# MAIN_BORAD.net
KiCad netlist of a schematic drawn in Altium Designer
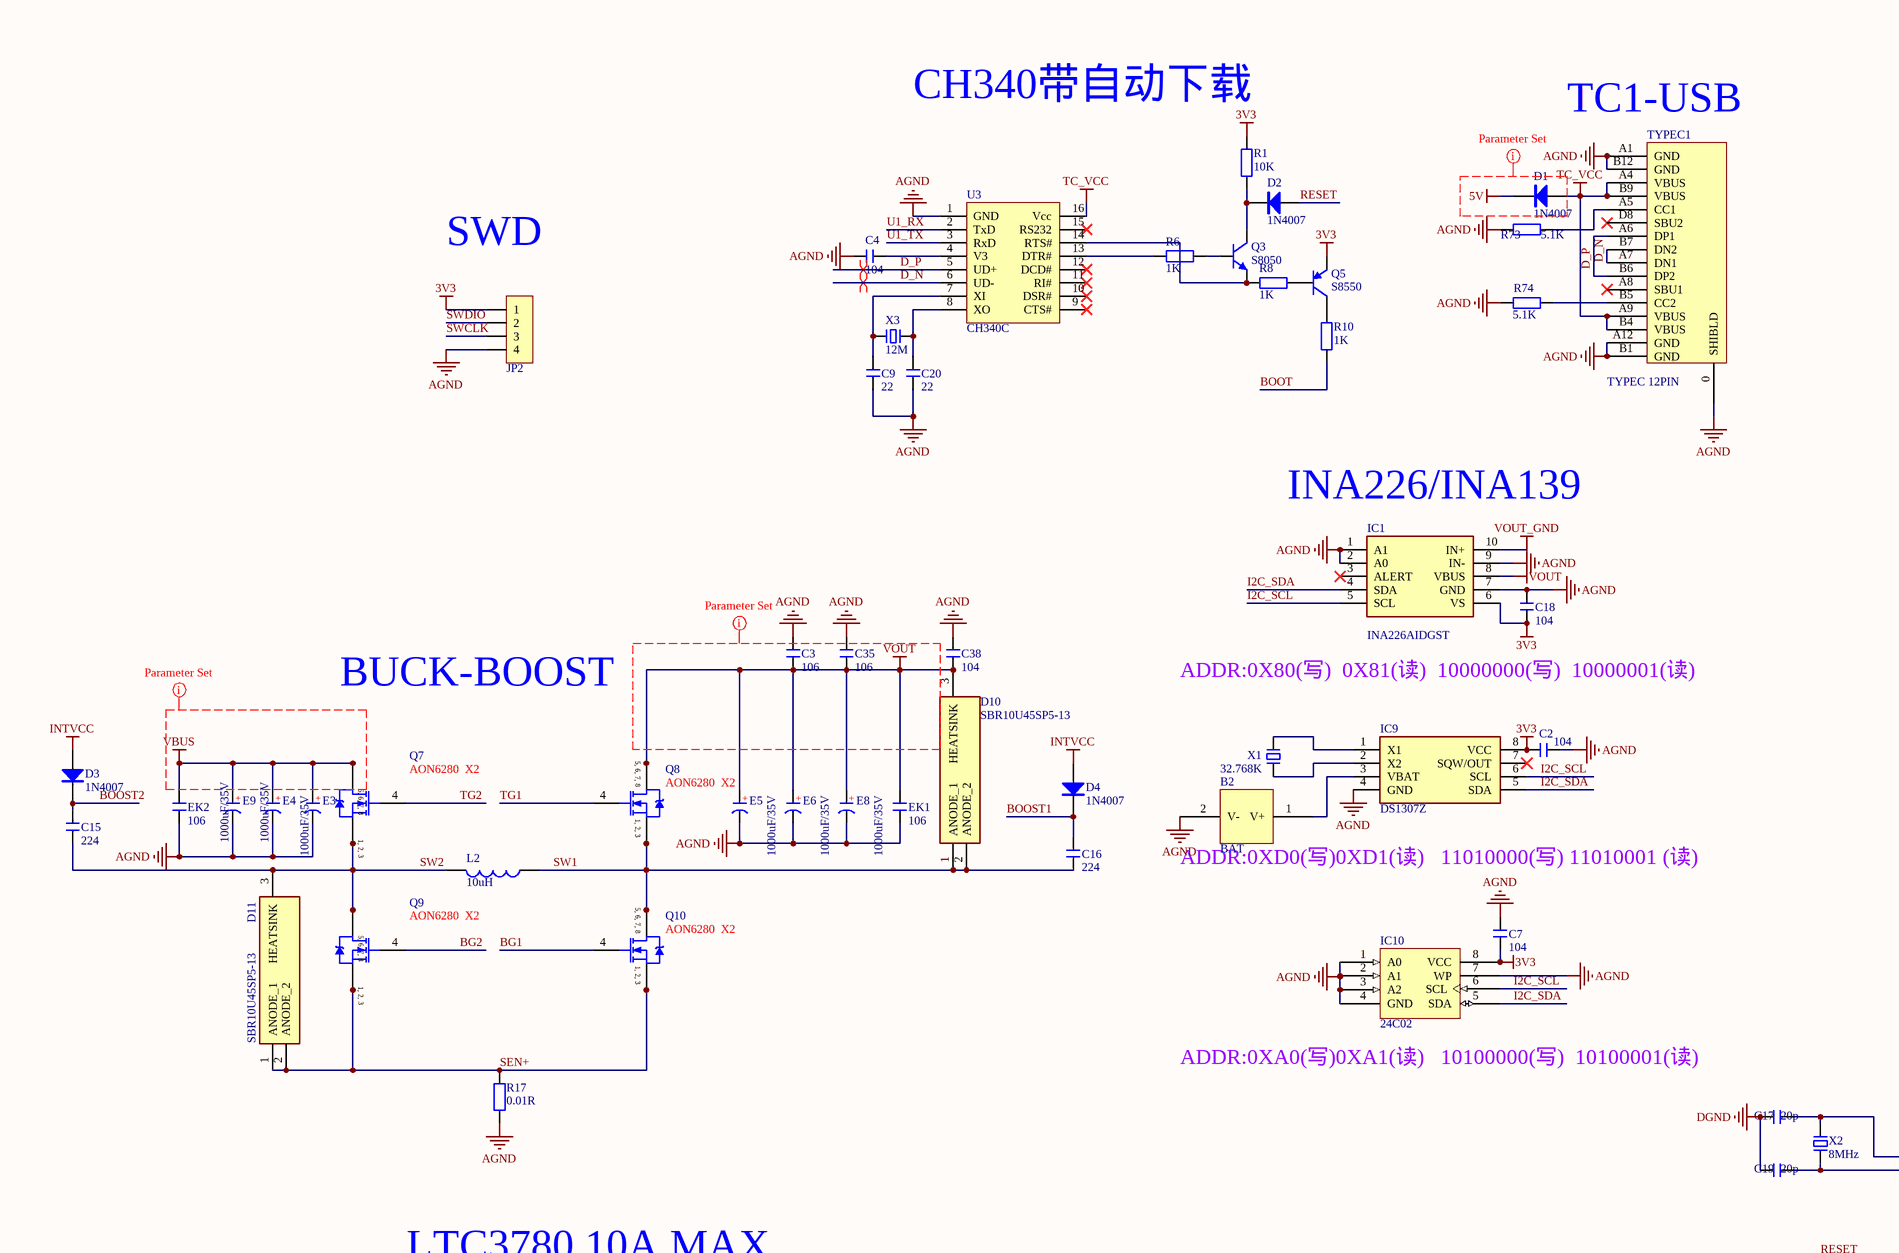
[diagram p0: MAIN_BORAD.SchDoc, top left]
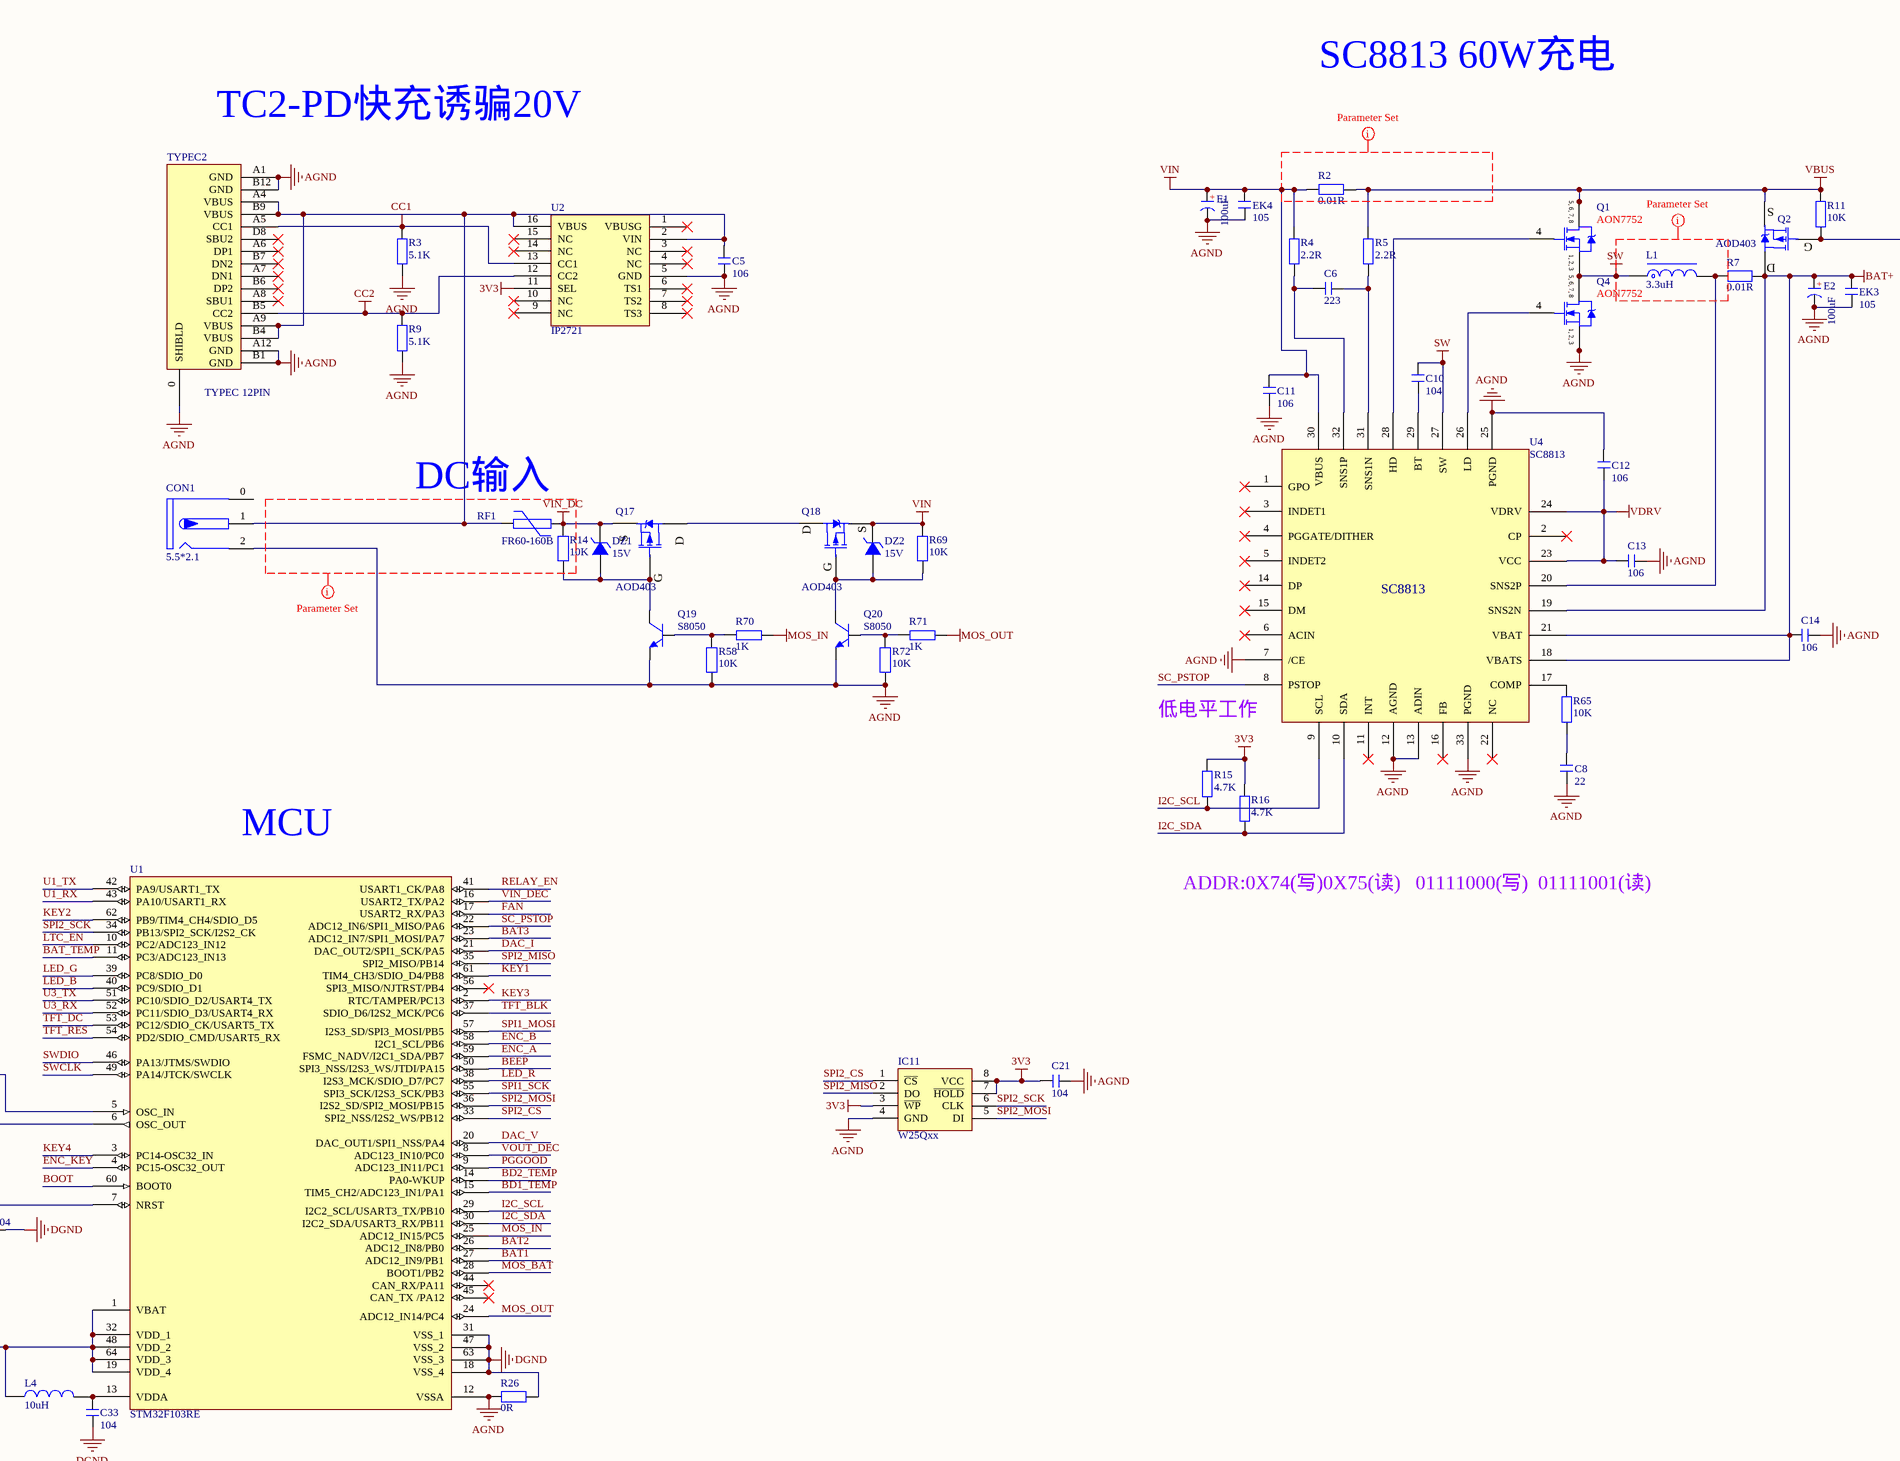
[diagram p1: MAIN_BORAD.SchDoc, top middle]
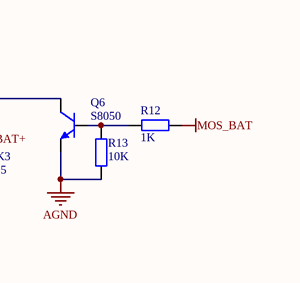
[diagram p2: MAIN_BORAD.SchDoc, top right]
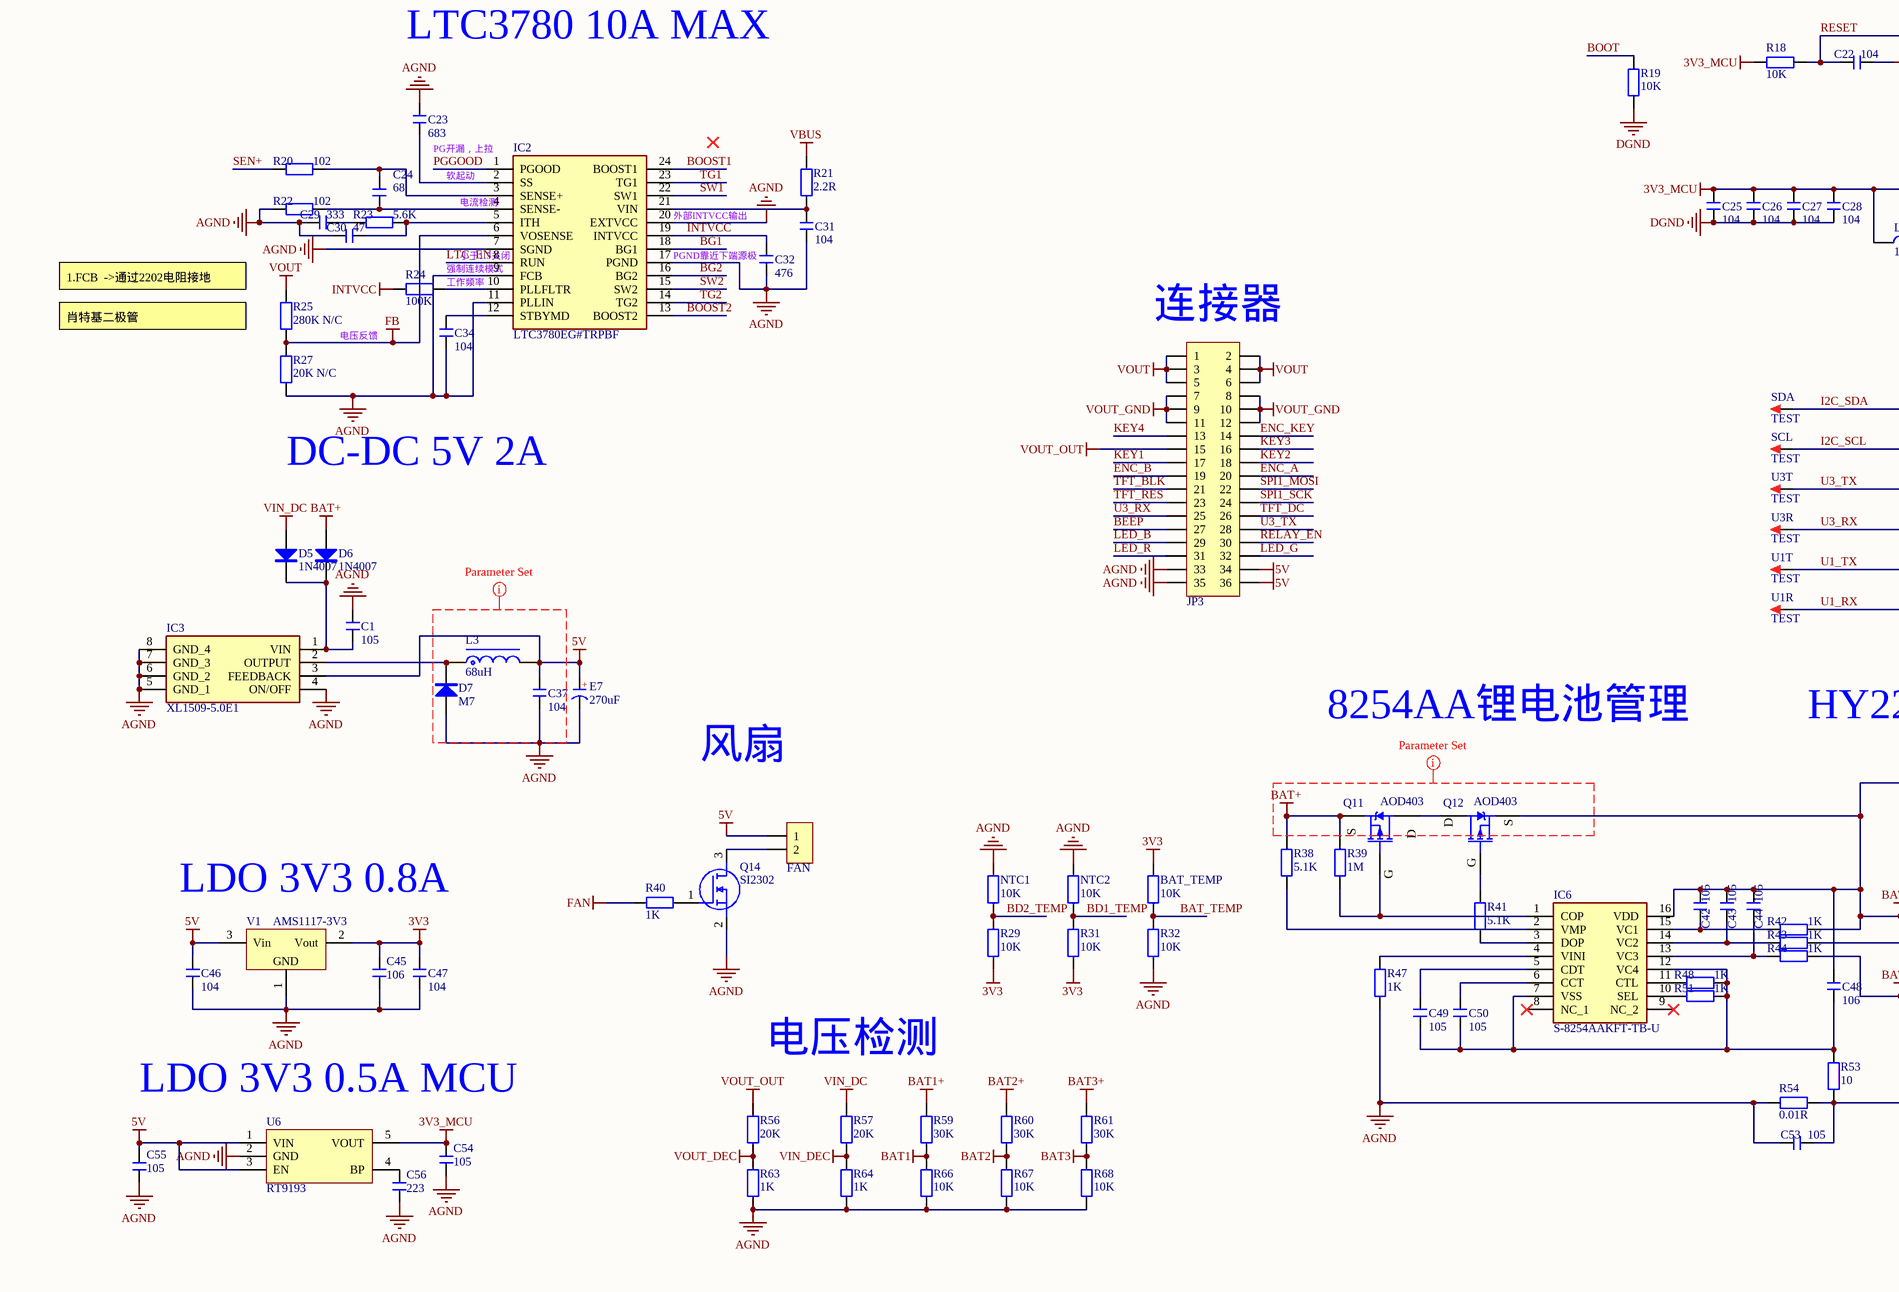
[diagram p3: MAIN_BORAD.SchDoc, bottom left]
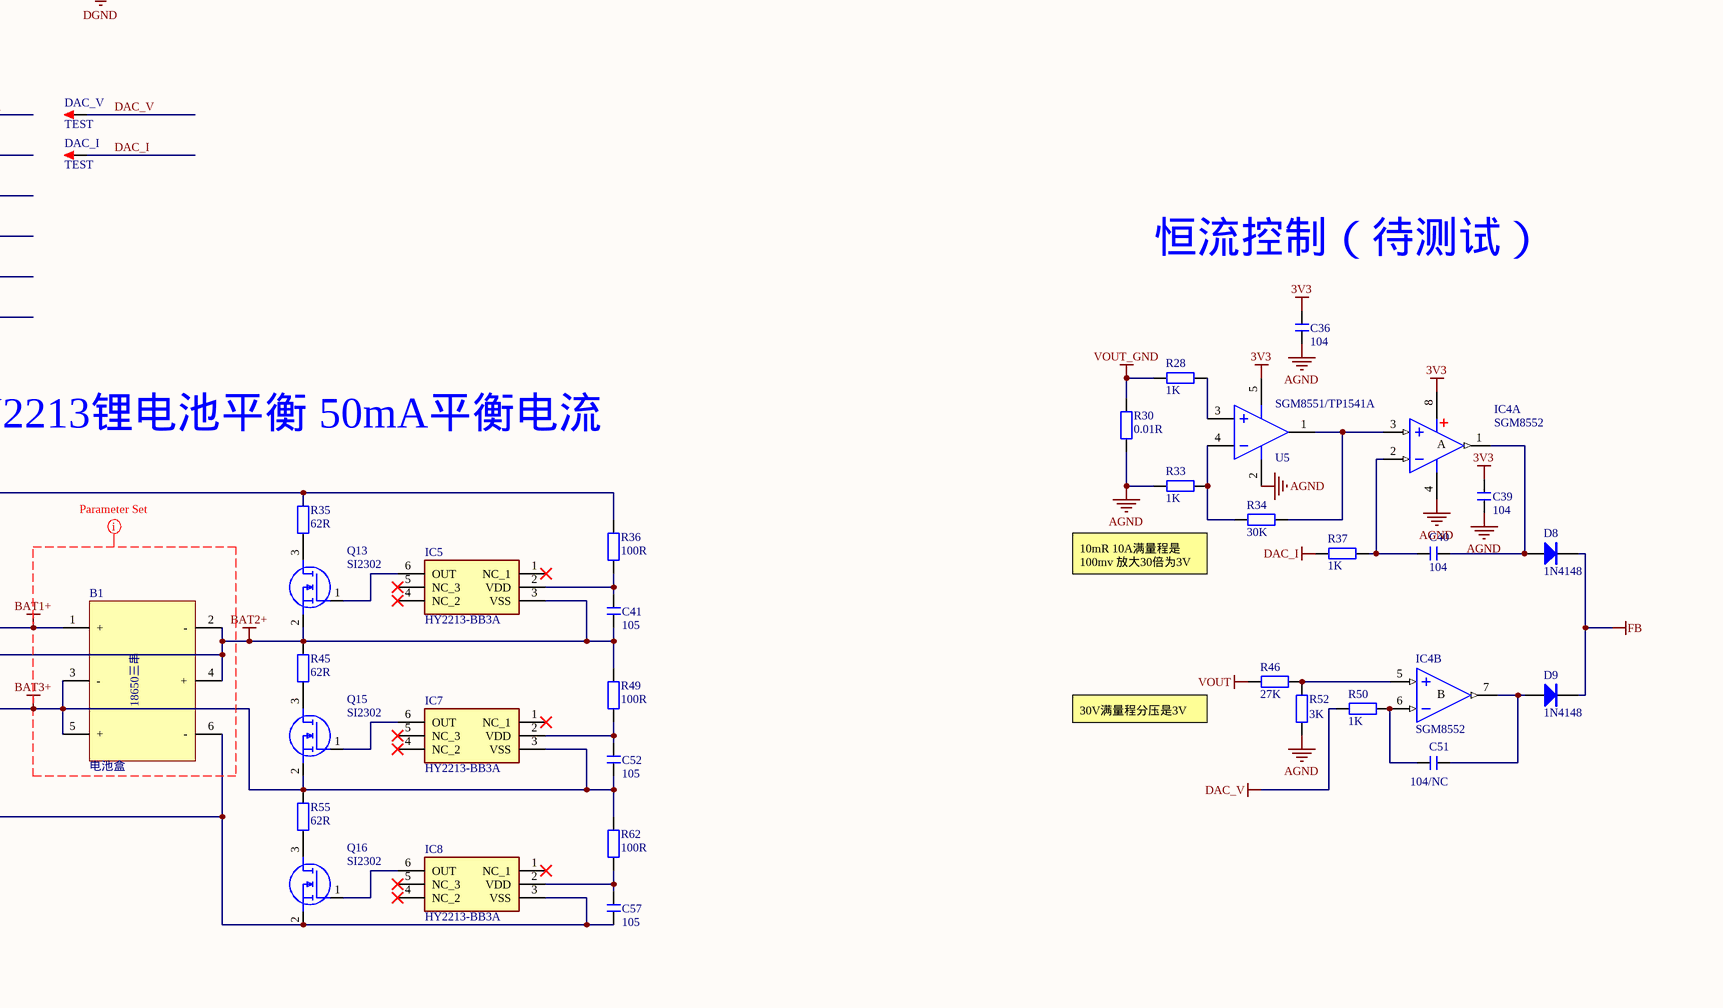
[diagram p4: MAIN_BORAD.SchDoc, bottom middle]

(export (version "E")
  (design (tool "Eeschema 10.0.6"))
  (components
    (comp (ref "B1") (value "电池盒") (footprint "18650") (libsource (lib "altium-import") (part "root_0_电池盒_")))
    (comp (ref "B2") (value "BAT") (footprint "bat") (libsource (lib "altium-import") (part "root_2_BAT_")))
    (comp (ref "BAT_TEMP")
      (value "10K")
      (footprint "R 0603_M")
      (description "贴片电阻")
      (fields (field (name "版权归属") "源创客"))
      (libsource (lib "3.1   - 电阻-电容-电感") (part "R"))
    )
    (comp (ref "C1")
      (value "105")
      (footprint "C 0603_M")
      (description "无极性贴片电容")
      (fields (field (name "版权归属") "源创客"))
      (libsource (lib "3.1   - 电阻-电容-电感") (part "C"))
    )
    (comp (ref "C2")
      (value "104")
      (footprint "C 0603_M")
      (description "无极性贴片电容")
      (fields (field (name "版权归属") "源创客"))
      (libsource (lib "3.1   - 电阻-电容-电感") (part "C"))
    )
    (comp (ref "C3")
      (value "106")
      (footprint "C 0805_M")
      (description "无极性贴片电容")
      (fields (field (name "版权归属") "源创客"))
      (libsource (lib "3.1   - 电阻-电容-电感") (part "C"))
    )
    (comp (ref "C4")
      (value "104")
      (footprint "C 0603_M")
      (description "无极性贴片电容")
      (fields (field (name "版权归属") "源创客"))
      (libsource (lib "3.1   - 电阻-电容-电感") (part "C"))
    )
    (comp (ref "C5")
      (value "106")
      (footprint "C 0603_M")
      (description "无极性贴片电容")
      (fields (field (name "版权归属") "源创客"))
      (libsource (lib "3.1   - 电阻-电容-电感") (part "C"))
    )
    (comp (ref "C6")
      (value "223")
      (footprint "C 0603_M")
      (description "无极性贴片电容")
      (fields (field (name "版权归属") "源创客"))
      (libsource (lib "3.1   - 电阻-电容-电感") (part "C"))
    )
    (comp (ref "C7")
      (value "104")
      (footprint "C 0603_M")
      (description "无极性贴片电容")
      (fields (field (name "版权归属") "源创客"))
      (libsource (lib "3.1   - 电阻-电容-电感") (part "C"))
    )
    (comp (ref "C8")
      (value "22")
      (footprint "C 0603_M")
      (description "无极性贴片电容")
      (fields (field (name "版权归属") "源创客"))
      (libsource (lib "3.1   - 电阻-电容-电感") (part "C"))
    )
    (comp (ref "C9")
      (value "22")
      (footprint "C 0603_M")
      (description "无极性贴片电容")
      (fields (field (name "版权归属") "源创客"))
      (libsource (lib "3.1   - 电阻-电容-电感") (part "C"))
    )
    (comp (ref "C10")
      (value "104")
      (footprint "C 0603_M")
      (description "无极性贴片电容")
      (fields (field (name "版权归属") "源创客"))
      (libsource (lib "3.1   - 电阻-电容-电感") (part "C"))
    )
    (comp (ref "C11")
      (value "106")
      (footprint "C 0603_M")
      (description "无极性贴片电容")
      (fields (field (name "版权归属") "源创客"))
      (libsource (lib "3.1   - 电阻-电容-电感") (part "C"))
    )
    (comp (ref "C12")
      (value "106")
      (footprint "C 0603_M")
      (description "无极性贴片电容")
      (fields (field (name "版权归属") "源创客"))
      (libsource (lib "3.1   - 电阻-电容-电感") (part "C"))
    )
    (comp (ref "C13")
      (value "106")
      (footprint "C 0603_M")
      (description "无极性贴片电容")
      (fields (field (name "版权归属") "源创客"))
      (libsource (lib "3.1   - 电阻-电容-电感") (part "C"))
    )
    (comp (ref "C14")
      (value "106")
      (footprint "C 0603_M")
      (description "无极性贴片电容")
      (fields (field (name "版权归属") "源创客"))
      (libsource (lib "3.1   - 电阻-电容-电感") (part "C"))
    )
    (comp (ref "C15")
      (value "224")
      (footprint "C 0603_M")
      (description "无极性贴片电容")
      (fields (field (name "版权归属") "源创客"))
      (libsource (lib "3.1   - 电阻-电容-电感") (part "C"))
    )
    (comp (ref "C16")
      (value "224")
      (footprint "C 0603_M")
      (description "无极性贴片电容")
      (fields (field (name "版权归属") "源创客"))
      (libsource (lib "3.1   - 电阻-电容-电感") (part "C"))
    )
    (comp (ref "C17")
      (value "20p")
      (footprint "C 0603_M")
      (description "无极性贴片电容")
      (fields (field (name "版权归属") "源创客"))
      (libsource (lib "3.1   - 电阻-电容-电感") (part "C"))
    )
    (comp (ref "C18")
      (value "104")
      (footprint "C 0603_M")
      (description "无极性贴片电容")
      (fields (field (name "版权归属") "源创客"))
      (libsource (lib "3.1   - 电阻-电容-电感") (part "C"))
    )
    (comp (ref "C19")
      (value "20p")
      (footprint "C 0603_M")
      (description "无极性贴片电容")
      (fields (field (name "版权归属") "源创客"))
      (libsource (lib "3.1   - 电阻-电容-电感") (part "C"))
    )
    (comp (ref "C20")
      (value "22")
      (footprint "C 0603_M")
      (description "无极性贴片电容")
      (fields (field (name "版权归属") "源创客"))
      (libsource (lib "3.1   - 电阻-电容-电感") (part "C"))
    )
    (comp (ref "C21")
      (value "104")
      (footprint "C 0603_M")
      (description "无极性贴片电容")
      (fields (field (name "版权归属") "源创客"))
      (libsource (lib "3.1   - 电阻-电容-电感") (part "C"))
    )
    (comp (ref "C22")
      (value "104")
      (footprint "C 0603_M")
      (description "无极性贴片电容")
      (fields (field (name "版权归属") "源创客"))
      (libsource (lib "3.1   - 电阻-电容-电感") (part "C"))
    )
    (comp (ref "C23")
      (value "683")
      (footprint "C 0603_M")
      (description "无极性贴片电容")
      (fields (field (name "版权归属") "源创客"))
      (libsource (lib "3.1   - 电阻-电容-电感") (part "C"))
    )
    (comp (ref "C24")
      (value "68")
      (footprint "C 0603_M")
      (description "无极性贴片电容")
      (fields (field (name "版权归属") "源创客"))
      (libsource (lib "3.1   - 电阻-电容-电感") (part "C"))
    )
    (comp (ref "C25")
      (value "104")
      (footprint "C 0603_M")
      (description "无极性贴片电容")
      (fields (field (name "版权归属") "源创客"))
      (libsource (lib "3.1   - 电阻-电容-电感") (part "C"))
    )
    (comp (ref "C26")
      (value "104")
      (footprint "C 0603_M")
      (description "无极性贴片电容")
      (fields (field (name "版权归属") "源创客"))
      (libsource (lib "3.1   - 电阻-电容-电感") (part "C"))
    )
    (comp (ref "C27")
      (value "104")
      (footprint "C 0603_M")
      (description "无极性贴片电容")
      (fields (field (name "版权归属") "源创客"))
      (libsource (lib "3.1   - 电阻-电容-电感") (part "C"))
    )
    (comp (ref "C28")
      (value "104")
      (footprint "C 0603_M")
      (description "无极性贴片电容")
      (fields (field (name "版权归属") "源创客"))
      (libsource (lib "3.1   - 电阻-电容-电感") (part "C"))
    )
    (comp (ref "C29")
      (value "333")
      (footprint "C 0603_M")
      (description "无极性贴片电容")
      (fields (field (name "版权归属") "源创客"))
      (libsource (lib "3.1   - 电阻-电容-电感") (part "C"))
    )
    (comp (ref "C30")
      (value "47")
      (footprint "C 0603_M")
      (description "无极性贴片电容")
      (fields (field (name "版权归属") "源创客"))
      (libsource (lib "3.1   - 电阻-电容-电感") (part "C"))
    )
    (comp (ref "C31")
      (value "104")
      (footprint "C 0603_M")
      (description "无极性贴片电容")
      (fields (field (name "版权归属") "源创客"))
      (libsource (lib "3.1   - 电阻-电容-电感") (part "C"))
    )
    (comp (ref "C32")
      (value "476")
      (footprint "C 0603_M")
      (description "无极性贴片电容")
      (fields (field (name "版权归属") "源创客"))
      (libsource (lib "3.1   - 电阻-电容-电感") (part "C"))
    )
    (comp (ref "C33")
      (value "104")
      (footprint "C 0603_M")
      (description "无极性贴片电容")
      (fields (field (name "版权归属") "源创客"))
      (libsource (lib "3.1   - 电阻-电容-电感") (part "C"))
    )
    (comp (ref "C34")
      (value "104")
      (footprint "C 0603_M")
      (description "无极性贴片电容")
      (fields (field (name "版权归属") "源创客"))
      (libsource (lib "3.1   - 电阻-电容-电感") (part "C"))
    )
    (comp (ref "C35")
      (value "106")
      (footprint "C 0805_M")
      (description "无极性贴片电容")
      (fields (field (name "版权归属") "源创客"))
      (libsource (lib "3.1   - 电阻-电容-电感") (part "C"))
    )
    (comp (ref "C36")
      (value "104")
      (footprint "C 0603_M")
      (description "无极性贴片电容")
      (fields (field (name "版权归属") "源创客"))
      (libsource (lib "3.1   - 电阻-电容-电感") (part "C"))
    )
    (comp (ref "C37")
      (value "104")
      (footprint "C 0603_M")
      (description "无极性贴片电容")
      (fields (field (name "版权归属") "源创客"))
      (libsource (lib "3.1   - 电阻-电容-电感") (part "C"))
    )
    (comp (ref "C38")
      (value "104")
      (footprint "C 0805_M")
      (description "无极性贴片电容")
      (fields (field (name "版权归属") "源创客"))
      (libsource (lib "3.1   - 电阻-电容-电感") (part "C"))
    )
    (comp (ref "C39")
      (value "104")
      (footprint "C 0603_M")
      (description "无极性贴片电容")
      (fields (field (name "版权归属") "源创客"))
      (libsource (lib "3.1   - 电阻-电容-电感") (part "C"))
    )
    (comp (ref "C40")
      (value "104")
      (footprint "C 0603_M")
      (description "无极性贴片电容")
      (fields (field (name "版权归属") "源创客"))
      (libsource (lib "3.1   - 电阻-电容-电感") (part "C"))
    )
    (comp (ref "C41")
      (value "105")
      (footprint "C 0603_M")
      (description "无极性贴片电容")
      (fields (field (name "版权归属") "源创客"))
      (libsource (lib "3.1   - 电阻-电容-电感") (part "C"))
    )
    (comp (ref "C42")
      (value "105")
      (footprint "C 0603_M")
      (description "无极性贴片电容")
      (fields (field (name "版权归属") "源创客"))
      (libsource (lib "3.1   - 电阻-电容-电感") (part "C"))
    )
    (comp (ref "C43")
      (value "105")
      (footprint "C 0603_M")
      (description "无极性贴片电容")
      (fields (field (name "版权归属") "源创客"))
      (libsource (lib "3.1   - 电阻-电容-电感") (part "C"))
    )
    (comp (ref "C44")
      (value "105")
      (footprint "C 0603_M")
      (description "无极性贴片电容")
      (fields (field (name "版权归属") "源创客"))
      (libsource (lib "3.1   - 电阻-电容-电感") (part "C"))
    )
    (comp (ref "C45")
      (value "106")
      (footprint "C 0603_M")
      (description "无极性贴片电容")
      (fields (field (name "版权归属") "源创客"))
      (libsource (lib "3.1   - 电阻-电容-电感") (part "C"))
    )
    (comp (ref "C46")
      (value "104")
      (footprint "C 0603_M")
      (description "无极性贴片电容")
      (fields (field (name "版权归属") "源创客"))
      (libsource (lib "3.1   - 电阻-电容-电感") (part "C"))
    )
    (comp (ref "C47")
      (value "104")
      (footprint "C 0603_M")
      (description "无极性贴片电容")
      (fields (field (name "版权归属") "源创客"))
      (libsource (lib "3.1   - 电阻-电容-电感") (part "C"))
    )
    (comp (ref "C48")
      (value "106")
      (footprint "C 0603_M")
      (description "无极性贴片电容")
      (fields (field (name "版权归属") "源创客"))
      (libsource (lib "3.1   - 电阻-电容-电感") (part "C"))
    )
    (comp (ref "C49")
      (value "105")
      (footprint "C 0603_M")
      (description "无极性贴片电容")
      (fields (field (name "版权归属") "源创客"))
      (libsource (lib "3.1   - 电阻-电容-电感") (part "C"))
    )
    (comp (ref "C50")
      (value "105")
      (footprint "C 0603_M")
      (description "无极性贴片电容")
      (fields (field (name "版权归属") "源创客"))
      (libsource (lib "3.1   - 电阻-电容-电感") (part "C"))
    )
    (comp (ref "C51")
      (value "104/NC")
      (footprint "C 0603_M")
      (description "无极性贴片电容")
      (fields (field (name "版权归属") "源创客"))
      (libsource (lib "3.1   - 电阻-电容-电感") (part "C"))
    )
    (comp (ref "C52")
      (value "105")
      (footprint "C 0603_M")
      (description "无极性贴片电容")
      (fields (field (name "版权归属") "源创客"))
      (libsource (lib "3.1   - 电阻-电容-电感") (part "C"))
    )
    (comp (ref "C53")
      (value "105")
      (footprint "C 0603_M")
      (description "无极性贴片电容")
      (fields (field (name "版权归属") "源创客"))
      (libsource (lib "3.1   - 电阻-电容-电感") (part "C"))
    )
    (comp (ref "C54")
      (value "105")
      (footprint "C 0603_M")
      (description "无极性贴片电容")
      (fields (field (name "版权归属") "源创客"))
      (libsource (lib "3.1   - 电阻-电容-电感") (part "C"))
    )
    (comp (ref "C55")
      (value "105")
      (footprint "C 0603_M")
      (description "无极性贴片电容")
      (fields (field (name "版权归属") "源创客"))
      (libsource (lib "3.1   - 电阻-电容-电感") (part "C"))
    )
    (comp (ref "C56")
      (value "223")
      (footprint "C 0603_M")
      (description "无极性贴片电容")
      (fields (field (name "版权归属") "源创客"))
      (libsource (lib "3.1   - 电阻-电容-电感") (part "C"))
    )
    (comp (ref "C57")
      (value "105")
      (footprint "C 0603_M")
      (description "无极性贴片电容")
      (fields (field (name "版权归属") "源创客"))
      (libsource (lib "3.1   - 电阻-电容-电感") (part "C"))
    )
    (comp (ref "CON1")
      (value "5.5*2.1")
      (footprint "DC-005P")
      (description "带屏蔽DC电源接口")
      (fields (field (name "版权归属") "源创客"))
      (libsource (lib "4.1   - 接口类") (part "DC-005P"))
    )
    (comp (ref "D1")
      (value "1N4007")
      (footprint "SOD-123")
      (description "整流二极管")
      (fields (field (name "版权归属") "源创客"))
      (libsource (lib "8.1   - 二极管-整流桥") (part "1N4007"))
    )
    (comp (ref "D2")
      (value "1N4007")
      (footprint "SOD-123")
      (description "整流二极管")
      (fields (field (name "版权归属") "源创客"))
      (libsource (lib "8.1   - 二极管-整流桥") (part "1N4007"))
    )
    (comp (ref "D3")
      (value "1N4007")
      (footprint "SOD-123")
      (description "整流二极管")
      (fields (field (name "版权归属") "源创客"))
      (libsource (lib "8.1   - 二极管-整流桥") (part "1N4007"))
    )
    (comp (ref "D4")
      (value "1N4007")
      (footprint "SOD-123")
      (description "整流二极管")
      (fields (field (name "版权归属") "源创客"))
      (libsource (lib "8.1   - 二极管-整流桥") (part "1N4007"))
    )
    (comp (ref "D5")
      (value "1N4007")
      (footprint "SOD-123")
      (description "整流二极管")
      (fields (field (name "版权归属") "源创客"))
      (libsource (lib "8.1   - 二极管-整流桥") (part "1N4007"))
    )
    (comp (ref "D6")
      (value "1N4007")
      (footprint "SOD-123")
      (description "整流二极管")
      (fields (field (name "版权归属") "源创客"))
      (libsource (lib "8.1   - 二极管-整流桥") (part "1N4007"))
    )
    (comp (ref "D7")
      (value "M7")
      (footprint "SMA")
      (description "整流二极管")
      (fields (field (name "版权归属") "源创客"))
      (libsource (lib "8.1   - 二极管-整流桥") (part "M7"))
    )
    (comp (ref "D8")
      (value "1N4148")
      (footprint "SOD-323")
      (description "高速开关二极管")
      (fields (field (name "版权归属") "源创客"))
      (libsource (lib "8.1   - 二极管-整流桥") (part "1N4148"))
    )
    (comp (ref "D9")
      (value "1N4148")
      (footprint "SOD-323")
      (description "高速开关二极管")
      (fields (field (name "版权归属") "源创客"))
      (libsource (lib "8.1   - 二极管-整流桥") (part "1N4148"))
    )
    (comp (ref "D10")
      (value "SBR10U45SP5-13")
      (footprint "PDS104013")
      (description "Schottky Diode")
      (fields (field (name "MOUSER PART NUMBER") "621-SBR10U45SP5-13"))
      (libsource (lib "*") (part "SBR10U45SP5-13"))
    )
    (comp (ref "D11")
      (value "SBR10U45SP5-13")
      (footprint "PDS104013")
      (description "Schottky Diode")
      (fields (field (name "MOUSER PART NUMBER") "621-SBR10U45SP5-13"))
      (libsource (lib "*") (part "SBR10U45SP5-13"))
    )
    (comp (ref "DAC_I")
      (value "TEST")
      (footprint "TEST 1")
      (description "测试点")
      (fields (field (name "版权归属") "源创客"))
      (libsource (lib "15.1 - 未分类器件") (part "TEST"))
    )
    (comp (ref "DAC_V")
      (value "TEST")
      (footprint "TEST 1")
      (description "测试点")
      (fields (field (name "版权归属") "源创客"))
      (libsource (lib "15.1 - 未分类器件") (part "TEST"))
    )
    (comp (ref "DZ1")
      (value "15V")
      (footprint "DO-213AA")
      (description "12V/0.5W稳压管")
      (fields (field (name "版权归属") "源创客"))
      (libsource (lib "8.1   - 二极管-整流桥") (part "1N4106"))
    )
    (comp (ref "DZ2")
      (value "15V")
      (footprint "DO-213AA")
      (description "12V/0.5W稳压管")
      (fields (field (name "版权归属") "源创客"))
      (libsource (lib "8.1   - 二极管-整流桥") (part "1N4106"))
    )
    (comp (ref "E1")
      (value "100uF")
      (footprint "CAP 2.0*5*11 - GD")
      (description "直插电解电容")
      (fields (field (name "版权归属") "源创客"))
      (libsource (lib "3.1   - 电阻-电容-电感") (part "C-CAP"))
    )
    (comp (ref "E2")
      (value "100uF")
      (footprint "CAP 2.5*5*11 - GD")
      (description "直插电解电容")
      (fields (field (name "版权归属") "源创客"))
      (libsource (lib "3.1   - 电阻-电容-电感") (part "C-CAP"))
    )
    (comp (ref "E3")
      (value "1000uF/35V")
      (footprint "CAP 5.0*10*20 - GD")
      (description "直插电解电容")
      (fields (field (name "版权归属") "源创客"))
      (libsource (lib "3.1   - 电阻-电容-电感") (part "C-CAP"))
    )
    (comp (ref "E4")
      (value "1000uF/35V")
      (footprint "CAP 5.0*10*20 - GD")
      (description "直插电解电容")
      (fields (field (name "版权归属") "源创客"))
      (libsource (lib "3.1   - 电阻-电容-电感") (part "C-CAP"))
    )
    (comp (ref "E5")
      (value "1000uF/35V")
      (footprint "CAP 5.0*10*20 - GD")
      (description "直插电解电容")
      (fields (field (name "版权归属") "源创客"))
      (libsource (lib "3.1   - 电阻-电容-电感") (part "C-CAP"))
    )
    (comp (ref "E6")
      (value "1000uF/35V")
      (footprint "CAP 5.0*10*20 - GD")
      (description "直插电解电容")
      (fields (field (name "版权归属") "源创客"))
      (libsource (lib "3.1   - 电阻-电容-电感") (part "C-CAP"))
    )
    (comp (ref "E7")
      (value "270uF")
      (footprint "CAP 2.0*5*11 - GD")
      (description "直插电解电容")
      (fields (field (name "版权归属") "源创客"))
      (libsource (lib "3.1   - 电阻-电容-电感") (part "C-CAP"))
    )
    (comp (ref "E8")
      (value "1000uF/35V")
      (footprint "CAP 5.0*10*20 - GD")
      (description "直插电解电容")
      (fields (field (name "版权归属") "源创客"))
      (libsource (lib "3.1   - 电阻-电容-电感") (part "C-CAP"))
    )
    (comp (ref "E9")
      (value "1000uF/35V")
      (footprint "CAP 5.0*10*20 - GD")
      (description "直插电解电容")
      (fields (field (name "版权归属") "源创客"))
      (libsource (lib "3.1   - 电阻-电容-电感") (part "C-CAP"))
    )
    (comp (ref "EK1")
      (value "106")
      (footprint "C 1210_M")
      (description "无极性贴片电容")
      (fields (field (name "版权归属") "源创客"))
      (libsource (lib "3.1   - 电阻-电容-电感") (part "C"))
    )
    (comp (ref "EK2")
      (value "106")
      (footprint "C 1210_M")
      (description "无极性贴片电容")
      (fields (field (name "版权归属") "源创客"))
      (libsource (lib "3.1   - 电阻-电容-电感") (part "C"))
    )
    (comp (ref "EK3")
      (value "105")
      (footprint "C 1206_M")
      (description "无极性贴片电容")
      (fields (field (name "版权归属") "源创客"))
      (libsource (lib "3.1   - 电阻-电容-电感") (part "C"))
    )
    (comp (ref "EK4")
      (value "105")
      (footprint "C 1206_M")
      (description "无极性贴片电容")
      (fields (field (name "版权归属") "源创客"))
      (libsource (lib "3.1   - 电阻-电容-电感") (part "C"))
    )
    (comp (ref "FAN")
      (value "HDR-1X2")
      (footprint "XH2.54-LI-2P")
      (description "2P接插件")
      (fields (field (name "版权归属") "源创客"))
      (libsource (lib "4.5   - 接插件-脚距2.54") (part "Header 2"))
    )
    (comp (ref "IC1")
      (value "INA226AIDGST")
      (footprint "SamacSys:SOP50P490X110-10N")
      (description "Integrated Circuit")
      (fields (field (name "MOUSER PART NUMBER") "595-INA226AIDGST"))
      (libsource (lib "*") (part "INA226AIDGST"))
    )
    (comp (ref "IC2")
      (value "LTC3780EG#TRPBF")
      (footprint "SamacSys:SOP65P780X200-24N")
      (description "Integrated Circuit")
      (fields (field (name "MOUSER PART NUMBER") "584-LTC3780EG#TRPBF"))
      (libsource (lib "altium-import") (part "root_0_LTC3780EG#TRPBF_"))
    )
    (comp (ref "IC3")
      (value "XL1509-5.0E1")
      (footprint "MAIN_PCH:SOIC127P600X175-8N")
      (description "Integrated Circuit")
      (libsource (lib "*") (part "XL1509-5.0E1"))
    )
    (comp (ref "IC4")
      (value "SGM8552")
      (footprint "SOP8_M")
      (description "双路运放")
      (fields (field (name "版权归属") "源创客"))
      (libsource (lib "1.1   - IC芯片") (part "LM358"))
    )
    (comp (ref "IC5")
      (value "HY2213-BB3A")
      (footprint "SamacSys:SOT95P280X140-6N")
      (description "Integrated Circuit")
      (libsource (lib "*") (part "HY2213-BB3A"))
    )
    (comp (ref "IC6")
      (value "S-8254AAKFT-TB-U")
      (footprint "SamacSys:SOP65P640X110-16N")
      (description "Integrated Circuit")
      (fields (field (name "MOUSER PART NUMBER") "628-S-8254AAKFT-TB-G"))
      (libsource (lib "altium-import") (part "root_0_S-8254AAKFT-TB-U_"))
    )
    (comp (ref "IC7")
      (value "HY2213-BB3A")
      (footprint "SamacSys:SOT95P280X140-6N")
      (description "Integrated Circuit")
      (libsource (lib "*") (part "HY2213-BB3A"))
    )
    (comp (ref "IC8")
      (value "HY2213-BB3A")
      (footprint "SamacSys:SOT95P280X140-6N")
      (description "Integrated Circuit")
      (libsource (lib "*") (part "HY2213-BB3A"))
    )
    (comp (ref "IC9")
      (value "DS1307Z")
      (footprint "SOP8_M")
      (description "Integrated Circuit")
      (fields (field (name "MOUSER PART NUMBER") "700-DS1307Z-NR"))
      (libsource (lib "*") (part "DS1307Z"))
    )
    (comp (ref "IC10")
      (value "24C02")
      (footprint "SOP8_M")
      (description "外置EEPROM")
      (fields (field (name "版权归属") "源创客"))
      (libsource (lib "1.1   - IC芯片") (part "24Cxx"))
    )
    (comp (ref "IC11")
      (value "W25Qxx")
      (footprint "SOP8W_N")
      (description "外置Flash")
      (fields (field (name "版权归属") "源创客"))
      (libsource (lib "1.1   - IC芯片") (part "W25Qxx"))
    )
    (comp (ref "JP2")
      (value "HDR-1X4")
      (footprint "ZH1.5-WS-4P")
      (description "4P接插件")
      (fields (field (name "版权归属") "源创客"))
      (libsource (lib "4.3   - 接插件-脚距1.5") (part "Header 4"))
    )
    (comp (ref "JP3")
      (value "Header 2X11")
      (footprint "HDR2.54-WI-2x18P")
      (description "18*2P接插件")
      (fields (field (name "版权归属") "源创客"))
      (libsource (lib "4.5   - 接插件-脚距2.54") (part "Header 18X2"))
    )
    (comp (ref "L1")
      (value "3.3uH")
      (footprint "CDRH125")
      (description "功率屏蔽电感")
      (fields (field (name "版权归属") "源创客"))
      (libsource (lib "3.1   - 电阻-电容-电感") (part "L-CDRH"))
    )
    (comp (ref "L2")
      (value "10uH")
      (footprint "SER2010202MLD")
      (description "小功率贴片电感")
      (fields (field (name "版权归属") "源创客"))
      (libsource (lib "3.1   - 电阻-电容-电感") (part "L"))
    )
    (comp (ref "L3")
      (value "68uH")
      (footprint "CDRH74")
      (description "功率屏蔽电感")
      (fields (field (name "版权归属") "源创客"))
      (libsource (lib "3.1   - 电阻-电容-电感") (part "L-CDRH"))
    )
    (comp (ref "L4")
      (value "10uH")
      (footprint "L 0805")
      (description "小功率贴片电感")
      (fields (field (name "版权归属") "源创客"))
      (libsource (lib "3.1   - 电阻-电容-电感") (part "L"))
    )
    (comp (ref "NTC1")
      (value "10K")
      (footprint "R 0603_M")
      (description "贴片电阻")
      (fields (field (name "版权归属") "源创客"))
      (libsource (lib "3.1   - 电阻-电容-电感") (part "R"))
    )
    (comp (ref "NTC2")
      (value "10K")
      (footprint "R 0603_M")
      (description "贴片电阻")
      (fields (field (name "版权归属") "源创客"))
      (libsource (lib "3.1   - 电阻-电容-电感") (part "R"))
    )
    (comp (ref "Q1")
      (value "AON7752")
      (footprint "EMB20N03V")
      (description "HEXFET Power MOSFET")
      (fields (field (name "PUBLISHER") "Altium Limited"))
      (libsource (lib "IR Discrete MOSFET - Power") (part "IRF7473"))
    )
    (comp (ref "Q2")
      (value "AOD403")
      (footprint "TO252")
      (description "P沟道场效应管")
      (fields (field (name "版权归属") "源创客"))
      (libsource (lib "6.1   - 场效应管-可控硅") (part "D15P05"))
    )
    (comp (ref "Q3")
      (value "S8050")
      (footprint "SOT23-3M")
      (description "高频放大-NPN型")
      (fields (field (name "版权归属") "源创客"))
      (libsource (lib "6.2   - 三极管") (part "8050-SMD"))
    )
    (comp (ref "Q4")
      (value "AON7752")
      (footprint "EMB20N03V")
      (description "HEXFET Power MOSFET")
      (fields (field (name "PUBLISHER") "Altium Limited"))
      (libsource (lib "IR Discrete MOSFET - Power") (part "IRF7473"))
    )
    (comp (ref "Q5")
      (value "S8550")
      (footprint "SOT23-3M")
      (description "高频放大-PNP型")
      (fields (field (name "版权归属") "源创客"))
      (libsource (lib "6.2   - 三极管") (part "8550-SMD"))
    )
    (comp (ref "Q6")
      (value "S8050")
      (footprint "SOT23-3M")
      (description "高频放大-NPN型")
      (fields (field (name "版权归属") "源创客"))
      (libsource (lib "6.2   - 三极管") (part "8050-SMD"))
    )
    (comp (ref "Q7")
      (value "AON6280  X2")
      (footprint "TPH1R306PLL1Q")
      (description "HEXFET Power MOSFET")
      (fields (field (name "PUBLISHER") "Altium Limited"))
      (libsource (lib "IR Discrete MOSFET - Power") (part "IRF7473"))
    )
    (comp (ref "Q8")
      (value "AON6280  X2")
      (footprint "TPH1R306PLL1Q")
      (description "HEXFET Power MOSFET")
      (fields (field (name "PUBLISHER") "Altium Limited"))
      (libsource (lib "IR Discrete MOSFET - Power") (part "IRF7473"))
    )
    (comp (ref "Q9")
      (value "AON6280  X2")
      (footprint "TPH1R306PLL1Q")
      (description "HEXFET Power MOSFET")
      (fields (field (name "PUBLISHER") "Altium Limited"))
      (libsource (lib "IR Discrete MOSFET - Power") (part "IRF7473"))
    )
    (comp (ref "Q10")
      (value "AON6280  X2")
      (footprint "TPH1R306PLL1Q")
      (description "HEXFET Power MOSFET")
      (fields (field (name "PUBLISHER") "Altium Limited"))
      (libsource (lib "IR Discrete MOSFET - Power") (part "IRF7473"))
    )
    (comp (ref "Q11")
      (value "AOD403")
      (footprint "TO252")
      (description "P沟道场效应管")
      (fields (field (name "版权归属") "源创客"))
      (libsource (lib "6.1   - 场效应管-可控硅") (part "D15P05"))
    )
    (comp (ref "Q12")
      (value "AOD403")
      (footprint "TO252")
      (description "P沟道场效应管")
      (fields (field (name "版权归属") "源创客"))
      (libsource (lib "6.1   - 场效应管-可控硅") (part "D15P05"))
    )
    (comp (ref "Q13")
      (value "SI2302")
      (footprint "SOT23-3M")
      (description "MOSFET (N-Channel)")
      (fields (field (name "MOUSER PART NUMBER") "833-SI2302"))
      (libsource (lib "*") (part "SI2302"))
    )
    (comp (ref "Q14")
      (value "SI2302")
      (footprint "SamacSys:SI2302")
      (description "MOSFET (N-Channel)")
      (fields (field (name "MOUSER PART NUMBER") "833-SI2302"))
      (libsource (lib "*") (part "SI2302"))
    )
    (comp (ref "Q15")
      (value "SI2302")
      (footprint "SOT23-3M")
      (description "MOSFET (N-Channel)")
      (fields (field (name "MOUSER PART NUMBER") "833-SI2302"))
      (libsource (lib "*") (part "SI2302"))
    )
    (comp (ref "Q16")
      (value "SI2302")
      (footprint "SOT23-3M")
      (description "MOSFET (N-Channel)")
      (fields (field (name "MOUSER PART NUMBER") "833-SI2302"))
      (libsource (lib "*") (part "SI2302"))
    )
    (comp (ref "Q17")
      (value "AOD403")
      (footprint "TO252")
      (description "P沟道场效应管")
      (fields (field (name "版权归属") "源创客"))
      (libsource (lib "6.1   - 场效应管-可控硅") (part "D15P05"))
    )
    (comp (ref "Q18")
      (value "AOD403")
      (footprint "TO252")
      (description "P沟道场效应管")
      (fields (field (name "版权归属") "源创客"))
      (libsource (lib "6.1   - 场效应管-可控硅") (part "D15P05"))
    )
    (comp (ref "Q19")
      (value "S8050")
      (footprint "SOT23-3M")
      (description "高频放大-NPN型")
      (fields (field (name "版权归属") "源创客"))
      (libsource (lib "6.2   - 三极管") (part "8050-SMD"))
    )
    (comp (ref "Q20")
      (value "S8050")
      (footprint "SOT23-3M")
      (description "高频放大-NPN型")
      (fields (field (name "版权归属") "源创客"))
      (libsource (lib "6.2   - 三极管") (part "8050-SMD"))
    )
    (comp (ref "R1")
      (value "10K")
      (footprint "R 0603_M")
      (description "贴片电阻")
      (fields (field (name "版权归属") "源创客"))
      (libsource (lib "3.1   - 电阻-电容-电感") (part "R"))
    )
    (comp (ref "R2")
      (value "0.01R")
      (footprint "R 2512_M")
      (description "贴片电阻")
      (fields (field (name "版权归属") "源创客"))
      (libsource (lib "3.1   - 电阻-电容-电感") (part "R"))
    )
    (comp (ref "R3")
      (value "5.1K")
      (footprint "R 0603_M")
      (description "贴片电阻")
      (fields (field (name "版权归属") "源创客"))
      (libsource (lib "3.1   - 电阻-电容-电感") (part "R"))
    )
    (comp (ref "R4")
      (value "2.2R")
      (footprint "R 0603_M")
      (description "贴片电阻")
      (fields (field (name "版权归属") "源创客"))
      (libsource (lib "3.1   - 电阻-电容-电感") (part "R"))
    )
    (comp (ref "R5")
      (value "2.2R")
      (footprint "R 0603_M")
      (description "贴片电阻")
      (fields (field (name "版权归属") "源创客"))
      (libsource (lib "3.1   - 电阻-电容-电感") (part "R"))
    )
    (comp (ref "R6")
      (value "1K")
      (footprint "R 0603_M")
      (description "贴片电阻")
      (fields (field (name "版权归属") "源创客"))
      (libsource (lib "3.1   - 电阻-电容-电感") (part "R"))
    )
    (comp (ref "R7")
      (value "0.01R")
      (footprint "R 1210_M")
      (description "贴片电阻")
      (fields (field (name "版权归属") "源创客"))
      (libsource (lib "3.1   - 电阻-电容-电感") (part "R"))
    )
    (comp (ref "R8")
      (value "1K")
      (footprint "R 0603_M")
      (description "贴片电阻")
      (fields (field (name "版权归属") "源创客"))
      (libsource (lib "3.1   - 电阻-电容-电感") (part "R"))
    )
    (comp (ref "R9")
      (value "5.1K")
      (footprint "R 0603_M")
      (description "贴片电阻")
      (fields (field (name "版权归属") "源创客"))
      (libsource (lib "3.1   - 电阻-电容-电感") (part "R"))
    )
    (comp (ref "R10")
      (value "1K")
      (footprint "R 0603_M")
      (description "贴片电阻")
      (fields (field (name "版权归属") "源创客"))
      (libsource (lib "3.1   - 电阻-电容-电感") (part "R"))
    )
    (comp (ref "R11")
      (value "10K")
      (footprint "R 0603_M")
      (description "贴片电阻")
      (fields (field (name "版权归属") "源创客"))
      (libsource (lib "3.1   - 电阻-电容-电感") (part "R"))
    )
    (comp (ref "R12")
      (value "1K")
      (footprint "R 0603_M")
      (description "贴片电阻")
      (fields (field (name "版权归属") "源创客"))
      (libsource (lib "3.1   - 电阻-电容-电感") (part "R"))
    )
    (comp (ref "R13")
      (value "10K")
      (footprint "R 0603_M")
      (description "贴片电阻")
      (fields (field (name "版权归属") "源创客"))
      (libsource (lib "3.1   - 电阻-电容-电感") (part "R"))
    )
    (comp (ref "R14")
      (value "10K")
      (footprint "R 0603_M")
      (description "贴片电阻")
      (fields (field (name "版权归属") "源创客"))
      (libsource (lib "3.1   - 电阻-电容-电感") (part "R"))
    )
    (comp (ref "R15")
      (value "4.7K")
      (footprint "R 0603_M")
      (description "贴片电阻")
      (fields (field (name "版权归属") "源创客"))
      (libsource (lib "3.1   - 电阻-电容-电感") (part "R"))
    )
    (comp (ref "R16")
      (value "4.7K")
      (footprint "R 0603_M")
      (description "贴片电阻")
      (fields (field (name "版权归属") "源创客"))
      (libsource (lib "3.1   - 电阻-电容-电感") (part "R"))
    )
    (comp (ref "R17")
      (value "0.01R")
      (footprint "R 1210_M")
      (description "贴片电阻")
      (fields (field (name "版权归属") "源创客"))
      (libsource (lib "3.1   - 电阻-电容-电感") (part "R"))
    )
    (comp (ref "R18")
      (value "10K")
      (footprint "R 0603_M")
      (description "贴片电阻")
      (fields (field (name "版权归属") "源创客"))
      (libsource (lib "3.1   - 电阻-电容-电感") (part "R"))
    )
    (comp (ref "R19")
      (value "10K")
      (footprint "R 0603_M")
      (description "贴片电阻")
      (fields (field (name "版权归属") "源创客"))
      (libsource (lib "3.1   - 电阻-电容-电感") (part "R"))
    )
    (comp (ref "R20")
      (value "102")
      (footprint "R 0603_M")
      (description "贴片电阻")
      (fields (field (name "版权归属") "源创客"))
      (libsource (lib "3.1   - 电阻-电容-电感") (part "R"))
    )
    (comp (ref "R21")
      (value "2.2R")
      (footprint "R 0603_M")
      (description "贴片电阻")
      (fields (field (name "版权归属") "源创客"))
      (libsource (lib "3.1   - 电阻-电容-电感") (part "R"))
    )
    (comp (ref "R22")
      (value "102")
      (footprint "R 0603_M")
      (description "贴片电阻")
      (fields (field (name "版权归属") "源创客"))
      (libsource (lib "3.1   - 电阻-电容-电感") (part "R"))
    )
    (comp (ref "R23")
      (value "5.6K")
      (footprint "R 0603_M")
      (description "贴片电阻")
      (fields (field (name "版权归属") "源创客"))
      (libsource (lib "3.1   - 电阻-电容-电感") (part "R"))
    )
    (comp (ref "R24")
      (value "100K")
      (footprint "R 0603_M")
      (description "贴片电阻")
      (fields (field (name "版权归属") "源创客"))
      (libsource (lib "3.1   - 电阻-电容-电感") (part "R"))
    )
    (comp (ref "R25")
      (value "280K N/C")
      (footprint "R 0603_M")
      (description "贴片电阻")
      (fields (field (name "版权归属") "源创客"))
      (libsource (lib "3.1   - 电阻-电容-电感") (part "R"))
    )
    (comp (ref "R26")
      (value "0R")
      (footprint "R 0603_M")
      (description "贴片电阻")
      (fields (field (name "版权归属") "源创客"))
      (libsource (lib "3.1   - 电阻-电容-电感") (part "R"))
    )
    (comp (ref "R27")
      (value "20K N/C")
      (footprint "R 0603_M")
      (description "贴片电阻")
      (fields (field (name "版权归属") "源创客"))
      (libsource (lib "3.1   - 电阻-电容-电感") (part "R"))
    )
    (comp (ref "R28")
      (value "1K")
      (footprint "R 0603_M")
      (description "贴片电阻")
      (fields (field (name "版权归属") "源创客"))
      (libsource (lib "3.1   - 电阻-电容-电感") (part "R"))
    )
    (comp (ref "R29")
      (value "10K")
      (footprint "R 0603_M")
      (description "贴片电阻")
      (fields (field (name "版权归属") "源创客"))
      (libsource (lib "3.1   - 电阻-电容-电感") (part "R"))
    )
    (comp (ref "R30")
      (value "0.01R")
      (footprint "R 2512_M")
      (description "贴片电阻")
      (fields (field (name "版权归属") "源创客"))
      (libsource (lib "3.1   - 电阻-电容-电感") (part "R"))
    )
    (comp (ref "R31")
      (value "10K")
      (footprint "R 0603_M")
      (description "贴片电阻")
      (fields (field (name "版权归属") "源创客"))
      (libsource (lib "3.1   - 电阻-电容-电感") (part "R"))
    )
    (comp (ref "R32")
      (value "10K")
      (footprint "R 0603_M")
      (description "贴片电阻")
      (fields (field (name "版权归属") "源创客"))
      (libsource (lib "3.1   - 电阻-电容-电感") (part "R"))
    )
    (comp (ref "R33")
      (value "1K")
      (footprint "R 0603_M")
      (description "贴片电阻")
      (fields (field (name "版权归属") "源创客"))
      (libsource (lib "3.1   - 电阻-电容-电感") (part "R"))
    )
    (comp (ref "R34")
      (value "30K")
      (footprint "R 0603_M")
      (description "贴片电阻")
      (fields (field (name "版权归属") "源创客"))
      (libsource (lib "3.1   - 电阻-电容-电感") (part "R"))
    )
    (comp (ref "R35")
      (value "62R")
      (footprint "R 0805_M")
      (description "贴片电阻")
      (fields (field (name "版权归属") "源创客"))
      (libsource (lib "3.1   - 电阻-电容-电感") (part "R"))
    )
    (comp (ref "R36")
      (value "100R")
      (footprint "R 0603_M")
      (description "贴片电阻")
      (fields (field (name "版权归属") "源创客"))
      (libsource (lib "3.1   - 电阻-电容-电感") (part "R"))
    )
    (comp (ref "R37")
      (value "1K")
      (footprint "R 0603_M")
      (description "贴片电阻")
      (fields (field (name "版权归属") "源创客"))
      (libsource (lib "3.1   - 电阻-电容-电感") (part "R"))
    )
    (comp (ref "R38")
      (value "5.1K")
      (footprint "R 0603_M")
      (description "贴片电阻")
      (fields (field (name "版权归属") "源创客"))
      (libsource (lib "3.1   - 电阻-电容-电感") (part "R"))
    )
    (comp (ref "R39")
      (value "1M")
      (footprint "R 0603_M")
      (description "贴片电阻")
      (fields (field (name "版权归属") "源创客"))
      (libsource (lib "3.1   - 电阻-电容-电感") (part "R"))
    )
    (comp (ref "R40")
      (value "1K")
      (footprint "R 0603_M")
      (description "贴片电阻")
      (fields (field (name "版权归属") "源创客"))
      (libsource (lib "3.1   - 电阻-电容-电感") (part "R"))
    )
    (comp (ref "R41")
      (value "5.1K")
      (footprint "R 0603_M")
      (description "贴片电阻")
      (fields (field (name "版权归属") "源创客"))
      (libsource (lib "3.1   - 电阻-电容-电感") (part "R"))
    )
    (comp (ref "R42")
      (value "1K")
      (footprint "R 0603_M")
      (description "贴片电阻")
      (fields (field (name "版权归属") "源创客"))
      (libsource (lib "3.1   - 电阻-电容-电感") (part "R"))
    )
    (comp (ref "R43")
      (value "1K")
      (footprint "R 0603_M")
      (description "贴片电阻")
      (fields (field (name "版权归属") "源创客"))
      (libsource (lib "3.1   - 电阻-电容-电感") (part "R"))
    )
    (comp (ref "R44")
      (value "1K")
      (footprint "R 0603_M")
      (description "贴片电阻")
      (fields (field (name "版权归属") "源创客"))
      (libsource (lib "3.1   - 电阻-电容-电感") (part "R"))
    )
    (comp (ref "R45")
      (value "62R")
      (footprint "R 0805_M")
      (description "贴片电阻")
      (fields (field (name "版权归属") "源创客"))
      (libsource (lib "3.1   - 电阻-电容-电感") (part "R"))
    )
    (comp (ref "R46")
      (value "27K")
      (footprint "R 0603_M")
      (description "贴片电阻")
      (fields (field (name "版权归属") "源创客"))
      (libsource (lib "3.1   - 电阻-电容-电感") (part "R"))
    )
    (comp (ref "R47")
      (value "1K")
      (footprint "R 0603_M")
      (description "贴片电阻")
      (fields (field (name "版权归属") "源创客"))
      (libsource (lib "3.1   - 电阻-电容-电感") (part "R"))
    )
    (comp (ref "R48")
      (value "1K")
      (footprint "R 0603_M")
      (description "贴片电阻")
      (fields (field (name "版权归属") "源创客"))
      (libsource (lib "3.1   - 电阻-电容-电感") (part "R"))
    )
    (comp (ref "R49")
      (value "100R")
      (footprint "R 0603_M")
      (description "贴片电阻")
      (fields (field (name "版权归属") "源创客"))
      (libsource (lib "3.1   - 电阻-电容-电感") (part "R"))
    )
    (comp (ref "R50")
      (value "1K")
      (footprint "R 0603_M")
      (description "贴片电阻")
      (fields (field (name "版权归属") "源创客"))
      (libsource (lib "3.1   - 电阻-电容-电感") (part "R"))
    )
    (comp (ref "R51")
      (value "1K")
      (footprint "R 0603_M")
      (description "贴片电阻")
      (fields (field (name "版权归属") "源创客"))
      (libsource (lib "3.1   - 电阻-电容-电感") (part "R"))
    )
    (comp (ref "R52")
      (value "3K")
      (footprint "R 0603_M")
      (description "贴片电阻")
      (fields (field (name "版权归属") "源创客"))
      (libsource (lib "3.1   - 电阻-电容-电感") (part "R"))
    )
    (comp (ref "R53")
      (value "10")
      (footprint "R 0603_M")
      (description "贴片电阻")
      (fields (field (name "版权归属") "源创客"))
      (libsource (lib "3.1   - 电阻-电容-电感") (part "R"))
    )
    (comp (ref "R54")
      (value "0.01R")
      (footprint "R 2512_M")
      (description "贴片电阻")
      (fields (field (name "版权归属") "源创客"))
      (libsource (lib "3.1   - 电阻-电容-电感") (part "R"))
    )
    (comp (ref "R55")
      (value "62R")
      (footprint "R 0805_M")
      (description "贴片电阻")
      (fields (field (name "版权归属") "源创客"))
      (libsource (lib "3.1   - 电阻-电容-电感") (part "R"))
    )
    (comp (ref "R56")
      (value "20K")
      (footprint "R 0603_M")
      (description "贴片电阻")
      (fields (field (name "版权归属") "源创客"))
      (libsource (lib "3.1   - 电阻-电容-电感") (part "R"))
    )
    (comp (ref "R57")
      (value "20K")
      (footprint "R 0603_M")
      (description "贴片电阻")
      (fields (field (name "版权归属") "源创客"))
      (libsource (lib "3.1   - 电阻-电容-电感") (part "R"))
    )
    (comp (ref "R58")
      (value "10K")
      (footprint "R 0603_M")
      (description "贴片电阻")
      (fields (field (name "版权归属") "源创客"))
      (libsource (lib "3.1   - 电阻-电容-电感") (part "R"))
    )
    (comp (ref "R59")
      (value "30K")
      (footprint "R 0603_M")
      (description "贴片电阻")
      (fields (field (name "版权归属") "源创客"))
      (libsource (lib "3.1   - 电阻-电容-电感") (part "R"))
    )
    (comp (ref "R60")
      (value "30K")
      (footprint "R 0603_M")
      (description "贴片电阻")
      (fields (field (name "版权归属") "源创客"))
      (libsource (lib "3.1   - 电阻-电容-电感") (part "R"))
    )
    (comp (ref "R61")
      (value "30K")
      (footprint "R 0603_M")
      (description "贴片电阻")
      (fields (field (name "版权归属") "源创客"))
      (libsource (lib "3.1   - 电阻-电容-电感") (part "R"))
    )
    (comp (ref "R62")
      (value "100R")
      (footprint "R 0603_M")
      (description "贴片电阻")
      (fields (field (name "版权归属") "源创客"))
      (libsource (lib "3.1   - 电阻-电容-电感") (part "R"))
    )
    (comp (ref "R63")
      (value "1K")
      (footprint "R 0603_M")
      (description "贴片电阻")
      (fields (field (name "版权归属") "源创客"))
      (libsource (lib "3.1   - 电阻-电容-电感") (part "R"))
    )
    (comp (ref "R64")
      (value "1K")
      (footprint "R 0603_M")
      (description "贴片电阻")
      (fields (field (name "版权归属") "源创客"))
      (libsource (lib "3.1   - 电阻-电容-电感") (part "R"))
    )
    (comp (ref "R65")
      (value "10K")
      (footprint "R 0603_M")
      (description "贴片电阻")
      (fields (field (name "版权归属") "源创客"))
      (libsource (lib "3.1   - 电阻-电容-电感") (part "R"))
    )
    (comp (ref "R66")
      (value "10K")
      (footprint "R 0603_M")
      (description "贴片电阻")
      (fields (field (name "版权归属") "源创客"))
      (libsource (lib "3.1   - 电阻-电容-电感") (part "R"))
    )
    (comp (ref "R67")
      (value "10K")
      (footprint "R 0603_M")
      (description "贴片电阻")
      (fields (field (name "版权归属") "源创客"))
      (libsource (lib "3.1   - 电阻-电容-电感") (part "R"))
    )
    (comp (ref "R68")
      (value "10K")
      (footprint "R 0603_M")
      (description "贴片电阻")
      (fields (field (name "版权归属") "源创客"))
      (libsource (lib "3.1   - 电阻-电容-电感") (part "R"))
    )
    (comp (ref "R69")
      (value "10K")
      (footprint "R 0603_M")
      (description "贴片电阻")
      (fields (field (name "版权归属") "源创客"))
      (libsource (lib "3.1   - 电阻-电容-电感") (part "R"))
    )
    (comp (ref "R70")
      (value "1K")
      (footprint "R 0603_M")
      (description "贴片电阻")
      (fields (field (name "版权归属") "源创客"))
      (libsource (lib "3.1   - 电阻-电容-电感") (part "R"))
    )
    (comp (ref "R71")
      (value "1K")
      (footprint "R 0603_M")
      (description "贴片电阻")
      (fields (field (name "版权归属") "源创客"))
      (libsource (lib "3.1   - 电阻-电容-电感") (part "R"))
    )
    (comp (ref "R72")
      (value "10K")
      (footprint "R 0603_M")
      (description "贴片电阻")
      (fields (field (name "版权归属") "源创客"))
      (libsource (lib "3.1   - 电阻-电容-电感") (part "R"))
    )
    (comp (ref "R73")
      (value "5.1K")
      (footprint "R 0603_M")
      (description "贴片电阻")
      (fields (field (name "版权归属") "源创客"))
      (libsource (lib "3.1   - 电阻-电容-电感") (part "R"))
    )
    (comp (ref "R74")
      (value "5.1K")
      (footprint "R 0603_M")
      (description "贴片电阻")
      (fields (field (name "版权归属") "源创客"))
      (libsource (lib "3.1   - 电阻-电容-电感") (part "R"))
    )
    (comp (ref "RF1")
      (value "FR60-160B")
      (footprint "FR60-160B")
      (description "PPTC自恢复保险丝")
      (fields (field (name "版权归属") "源创客"))
      (libsource (lib "10.1 - 保险丝-晶振") (part "PPTC"))
    )
    (comp (ref "SCL")
      (value "TEST")
      (footprint "TEST 1")
      (description "测试点")
      (fields (field (name "版权归属") "源创客"))
      (libsource (lib "15.1 - 未分类器件") (part "TEST"))
    )
    (comp (ref "SDA")
      (value "TEST")
      (footprint "TEST 1")
      (description "测试点")
      (fields (field (name "版权归属") "源创客"))
      (libsource (lib "15.1 - 未分类器件") (part "TEST"))
    )
    (comp (ref "TYPEC1")
      (value "TYPEC 12PIN")
      (footprint "TYPEC_16P")
      (description "TPYEC接口 12PIN 的")
      (libsource (lib "altium-import") (part "root_0_TYPEC_"))
    )
    (comp (ref "TYPEC2")
      (value "TYPEC 12PIN")
      (footprint "TYPEC_16P")
      (description "TPYEC接口 12PIN 的")
      (libsource (lib "altium-import") (part "root_0_mirrored_TYPEC_"))
    )
    (comp (ref "U1")
      (value "STM32F103RE")
      (footprint "LQFP64 10X10_L")
      (description "32位STM单片机")
      (fields (field (name "版权归属") "源创客"))
      (libsource (lib "2.1   - STM32系列单片机") (part "STM32F103RE"))
    )
    (comp (ref "U1R")
      (value "TEST")
      (footprint "TEST 1")
      (description "测试点")
      (fields (field (name "版权归属") "源创客"))
      (libsource (lib "15.1 - 未分类器件") (part "TEST"))
    )
    (comp (ref "U1T")
      (value "TEST")
      (footprint "TEST 1")
      (description "测试点")
      (fields (field (name "版权归属") "源创客"))
      (libsource (lib "15.1 - 未分类器件") (part "TEST"))
    )
    (comp (ref "U2")
      (value "IP2721")
      (footprint "TSSOP16_M")
      (libsource (lib "altium-import") (part "root_0_mirrored_IP2721_"))
    )
    (comp (ref "U3")
      (value "CH340C")
      (footprint "SOP16_M")
      (description "串口转USB")
      (fields (field (name "版权归属") "源创客"))
      (libsource (lib "1.1   - IC芯片") (part "CH340G"))
    )
    (comp (ref "U3R")
      (value "TEST")
      (footprint "TEST 1")
      (description "测试点")
      (fields (field (name "版权归属") "源创客"))
      (libsource (lib "15.1 - 未分类器件") (part "TEST"))
    )
    (comp (ref "U3T")
      (value "TEST")
      (footprint "TEST 1")
      (description "测试点")
      (fields (field (name "版权归属") "源创客"))
      (libsource (lib "15.1 - 未分类器件") (part "TEST"))
    )
    (comp (ref "U4")
      (value "SC8813")
      (footprint "QFN40P400X400X80_HS-33N")
      (libsource (lib "MAIN_SCH") (part "SC8813"))
    )
    (comp (ref "U5")
      (value "SGM8551/TP1541A")
      (footprint "SOT23-5M")
      (description "轨到轨运算放大器")
      (libsource (lib "altium-import") (part "root_0_SGM8551XN_"))
    )
    (comp (ref "U6")
      (value "RT9193")
      (footprint "SOT23-5M")
      (description "LDO降压芯片")
      (libsource (lib "1.3   - 电源类芯片") (part "RT9193"))
    )
    (comp (ref "V1")
      (value "AMS1117-3V3")
      (footprint "SOT223_M")
      (description "三端稳压芯片")
      (fields (field (name "版权归属") "源创客"))
      (libsource (lib "1.3   - 电源类芯片") (part "AMS1117"))
    )
    (comp (ref "X1")
      (value "32.768K")
      (footprint "OSC-3x10-WS")
      (description "2脚无源脚晶振")
      (fields (field (name "版权归属") "源创客"))
      (libsource (lib "10.1 - 保险丝-晶振") (part "XTAL-2P"))
    )
    (comp (ref "X2")
      (value "8MHz")
      (footprint "OSC 5032-2P")
      (description "2脚无源脚晶振")
      (fields (field (name "版权归属") "源创客"))
      (libsource (lib "10.1 - 保险丝-晶振") (part "XTAL-2P"))
    )
    (comp (ref "X3")
      (value "12M")
      (footprint "OSC 3215-2P")
      (description "2脚无源脚晶振")
      (fields (field (name "版权归属") "源创客"))
      (libsource (lib "10.1 - 保险丝-晶振") (part "XTAL-2P"))
    )
  )
  (nets
    (net (code "1") (name "/BAT_TEMP") (class "Default")
      (node (ref "BAT_TEMP") (pin "2") (pinfunction "2_2") (pintype "passive"))
      (node (ref "R32") (pin "1") (pinfunction "1_1") (pintype "passive"))
      (node (ref "U1") (pin "11") (pinfunction "PC3/ADC123_IN13_11") (pintype "bidirectional"))
    )
    (net (code "2") (name "/BD1_TEMP") (class "Default")
      (node (ref "NTC2") (pin "2") (pinfunction "2_2") (pintype "passive"))
      (node (ref "R31") (pin "1") (pinfunction "1_1") (pintype "passive"))
      (node (ref "U1") (pin "15") (pinfunction "TIM5_CH2/ADC123_IN1/PA1_15") (pintype "bidirectional"))
    )
    (net (code "3") (name "/BD2_TEMP") (class "Default")
      (node (ref "NTC1") (pin "2") (pinfunction "2_2") (pintype "passive"))
      (node (ref "R29") (pin "1") (pinfunction "1_1") (pintype "passive"))
      (node (ref "U1") (pin "14") (pinfunction "PA0-WKUP_14") (pintype "bidirectional"))
    )
    (net (code "4") (name "/BEEP") (class "Default")
      (node (ref "JP3") (pin "27") (pinfunction "27_27") (pintype "passive"))
      (node (ref "U1") (pin "50") (pinfunction "SPI3_NSS/I2S3_WS/JTDI/PA15_50") (pintype "bidirectional"))
    )
    (net (code "5") (name "/BG1") (class "Default")
      (node (ref "IC2") (pin "18") (pinfunction "BG1_18") (pintype "passive"))
      (node (ref "Q10") (pin "4") (pinfunction "G_4") (pintype "passive"))
    )
    (net (code "6") (name "/BG2") (class "Default")
      (node (ref "IC2") (pin "16") (pinfunction "BG2_16") (pintype "passive"))
      (node (ref "Q9") (pin "4") (pinfunction "G_4") (pintype "passive"))
    )
    (net (code "7") (name "/BOOST1") (class "Default")
      (node (ref "C16") (pin "2") (pinfunction "2_2") (pintype "passive"))
      (node (ref "D4") (pin "2") (pinfunction "K_2") (pintype "passive"))
      (node (ref "IC2") (pin "24") (pinfunction "BOOST1_24") (pintype "passive"))
    )
    (net (code "8") (name "/BOOST2") (class "Default")
      (node (ref "C15") (pin "2") (pinfunction "2_2") (pintype "passive"))
      (node (ref "D3") (pin "2") (pinfunction "K_2") (pintype "passive"))
      (node (ref "IC2") (pin "13") (pinfunction "BOOST2_13") (pintype "passive"))
    )
    (net (code "9") (name "/BOOT") (class "Default")
      (node (ref "R10") (pin "2") (pinfunction "2_2") (pintype "passive"))
      (node (ref "R19") (pin "2") (pinfunction "2_2") (pintype "passive"))
      (node (ref "U1") (pin "60") (pinfunction "BOOT0_60") (pintype "input"))
    )
    (net (code "10") (name "/D_N") (class "Default")
      (node (ref "TYPEC1") (pin "A7") (pinfunction "DN1_A7") (pintype "passive"))
      (node (ref "TYPEC1") (pin "B7") (pinfunction "DN2_B7") (pintype "passive"))
      (node (ref "U3") (pin "6") (pinfunction "UD-_6") (pintype "passive"))
    )
    (net (code "11") (name "/D_P") (class "Default")
      (node (ref "TYPEC1") (pin "A6") (pinfunction "DP1_A6") (pintype "passive"))
      (node (ref "TYPEC1") (pin "B6") (pinfunction "DP2_B6") (pintype "passive"))
      (node (ref "U3") (pin "5") (pinfunction "UD+_5") (pintype "passive"))
    )
    (net (code "12") (name "/ENC_A") (class "Default")
      (node (ref "JP3") (pin "20") (pinfunction "20_20") (pintype "passive"))
      (node (ref "U1") (pin "59") (pinfunction "FSMC_NADV/I2C1_SDA/PB7_59") (pintype "bidirectional"))
    )
    (net (code "13") (name "/ENC_B") (class "Default")
      (node (ref "JP3") (pin "19") (pinfunction "19_19") (pintype "passive"))
      (node (ref "U1") (pin "58") (pinfunction "I2C1_SCL/PB6_58") (pintype "bidirectional"))
    )
    (net (code "14") (name "/ENC_KEY") (class "Default")
      (node (ref "JP3") (pin "14") (pinfunction "14_14") (pintype "passive"))
      (node (ref "U1") (pin "4") (pinfunction "PC15-OSC32_OUT_4") (pintype "bidirectional"))
    )
    (net (code "15") (name "/I2C_SCL") (class "Default")
      (node (ref "IC1") (pin "5") (pinfunction "SCL_5") (pintype "passive"))
      (node (ref "IC10") (pin "6") (pinfunction "SCL_6") (pintype "input"))
      (node (ref "IC9") (pin "6") (pinfunction "SCL_6") (pintype "passive"))
      (node (ref "R15") (pin "1") (pinfunction "1_1") (pintype "passive"))
      (node (ref "SCL") (pin "1") (pinfunction "1_1") (pintype "passive"))
      (node (ref "U1") (pin "29") (pinfunction "I2C2_SCL/USART3_TX/PB10_29") (pintype "bidirectional"))
      (node (ref "U4") (pin "9") (pinfunction "SCL_9") (pintype "passive"))
    )
    (net (code "16") (name "/I2C_SDA") (class "Default")
      (node (ref "IC1") (pin "4") (pinfunction "SDA_4") (pintype "passive"))
      (node (ref "IC10") (pin "5") (pinfunction "SDA_5") (pintype "bidirectional"))
      (node (ref "IC9") (pin "5") (pinfunction "SDA_5") (pintype "passive"))
      (node (ref "R16") (pin "1") (pinfunction "1_1") (pintype "passive"))
      (node (ref "SDA") (pin "1") (pinfunction "1_1") (pintype "passive"))
      (node (ref "U1") (pin "30") (pinfunction "I2C2_SDA/USART3_RX/PB11_30") (pintype "bidirectional"))
      (node (ref "U4") (pin "10") (pinfunction "SDA_10") (pintype "passive"))
    )
    (net (code "17") (name "/KEY1") (class "Default")
      (node (ref "JP3") (pin "17") (pinfunction "17_17") (pintype "passive"))
      (node (ref "U1") (pin "61") (pinfunction "TIM4_CH3/SDIO_D4/PB8_61") (pintype "bidirectional"))
    )
    (net (code "18") (name "/KEY2") (class "Default")
      (node (ref "JP3") (pin "18") (pinfunction "18_18") (pintype "passive"))
      (node (ref "U1") (pin "62") (pinfunction "PB9/TIM4_CH4/SDIO_D5_62") (pintype "bidirectional"))
    )
    (net (code "19") (name "/KEY3") (class "Default")
      (node (ref "JP3") (pin "16") (pinfunction "16_16") (pintype "passive"))
      (node (ref "U1") (pin "2") (pinfunction "RTC/TAMPER/PC13_2") (pintype "bidirectional"))
    )
    (net (code "20") (name "/KEY4") (class "Default")
      (node (ref "JP3") (pin "13") (pinfunction "13_13") (pintype "passive"))
      (node (ref "U1") (pin "3") (pinfunction "PC14-OSC32_IN_3") (pintype "bidirectional"))
    )
    (net (code "21") (name "/LED_B") (class "Default")
      (node (ref "JP3") (pin "29") (pinfunction "29_29") (pintype "passive"))
      (node (ref "U1") (pin "40") (pinfunction "PC9/SDIO_D1_40") (pintype "bidirectional"))
    )
    (net (code "22") (name "/LED_G") (class "Default")
      (node (ref "JP3") (pin "32") (pinfunction "32_32") (pintype "passive"))
      (node (ref "U1") (pin "39") (pinfunction "PC8/SDIO_D0_39") (pintype "bidirectional"))
    )
    (net (code "23") (name "/LED_R") (class "Default")
      (node (ref "JP3") (pin "31") (pinfunction "31_31") (pintype "passive"))
      (node (ref "U1") (pin "38") (pinfunction "I2S3_MCK/SDIO_D7/PC7_38") (pintype "bidirectional"))
    )
    (net (code "24") (name "/LTC_EN") (class "Default")
      (node (ref "IC2") (pin "8") (pinfunction "RUN_8") (pintype "passive"))
      (node (ref "U1") (pin "10") (pinfunction "PC2/ADC123_IN12_10") (pintype "bidirectional"))
    )
    (net (code "25") (name "/PGGOOD") (class "Default")
      (node (ref "IC2") (pin "1") (pinfunction "PGOOD_1") (pintype "passive"))
      (node (ref "U1") (pin "9") (pinfunction "ADC123_IN11/PC1_9") (pintype "bidirectional"))
    )
    (net (code "26") (name "/RELAY_EN") (class "Default")
      (node (ref "JP3") (pin "30") (pinfunction "30_30") (pintype "passive"))
      (node (ref "U1") (pin "41") (pinfunction "USART1_CK/PA8_41") (pintype "bidirectional"))
    )
    (net (code "27") (name "/RESET") (class "Default")
      (node (ref "C22") (pin "2") (pinfunction "2_2") (pintype "passive"))
      (node (ref "D2") (pin "1") (pinfunction "A_1") (pintype "passive"))
      (node (ref "R18") (pin "2") (pinfunction "2_2") (pintype "passive"))
      (node (ref "U1") (pin "7") (pinfunction "NRST_7") (pintype "bidirectional"))
    )
    (net (code "28") (name "/SC_PSTOP") (class "Default")
      (node (ref "U1") (pin "22") (pinfunction "ADC12_IN6/SPI1_MISO/PA6_22") (pintype "bidirectional"))
      (node (ref "U4") (pin "8") (pinfunction "PSTOP_8") (pintype "passive"))
    )
    (net (code "29") (name "/SEN+") (class "Default")
      (node (ref "D11") (pin "1") (pinfunction "ANODE_1_1") (pintype "passive"))
      (node (ref "D11") (pin "2") (pinfunction "ANODE_2_2") (pintype "passive"))
      (node (ref "Q10") (pin "1") (pinfunction "S_1") (pintype "passive"))
      (node (ref "Q10") (pin "2") (pinfunction "S_2") (pintype "passive"))
      (node (ref "Q10") (pin "3") (pinfunction "S_3") (pintype "passive"))
      (node (ref "Q9") (pin "1") (pinfunction "S_1") (pintype "passive"))
      (node (ref "Q9") (pin "2") (pinfunction "S_2") (pintype "passive"))
      (node (ref "Q9") (pin "3") (pinfunction "S_3") (pintype "passive"))
      (node (ref "R17") (pin "2") (pinfunction "2_2") (pintype "passive"))
      (node (ref "R20") (pin "2") (pinfunction "2_2") (pintype "passive"))
    )
    (net (code "30") (name "/SPI1_MOSI") (class "Default")
      (node (ref "JP3") (pin "22") (pinfunction "22_22") (pintype "passive"))
      (node (ref "U1") (pin "57") (pinfunction "I2S3_SD/SPI3_MOSI/PB5_57") (pintype "bidirectional"))
    )
    (net (code "31") (name "/SPI1_SCK") (class "Default")
      (node (ref "JP3") (pin "24") (pinfunction "24_24") (pintype "passive"))
      (node (ref "U1") (pin "55") (pinfunction "SPI3_SCK/I2S3_SCK/PB3_55") (pintype "bidirectional"))
    )
    (net (code "32") (name "/SPI2_CS") (class "Default")
      (node (ref "IC11") (pin "1") (pinfunction "~{CS}_1") (pintype "passive"))
      (node (ref "U1") (pin "33") (pinfunction "SPI2_NSS/I2S2_WS/PB12_33") (pintype "bidirectional"))
    )
    (net (code "33") (name "/SPI2_MISO") (class "Default")
      (node (ref "IC11") (pin "2") (pinfunction "DO_2") (pintype "passive"))
      (node (ref "U1") (pin "35") (pinfunction "SPI2_MISO/PB14_35") (pintype "bidirectional"))
    )
    (net (code "34") (name "/SPI2_MOSI") (class "Default")
      (node (ref "IC11") (pin "5") (pinfunction "DI_5") (pintype "passive"))
      (node (ref "U1") (pin "36") (pinfunction "I2S2_SD/SPI2_MOSI/PB15_36") (pintype "bidirectional"))
    )
    (net (code "35") (name "/SPI2_SCK") (class "Default")
      (node (ref "IC11") (pin "6") (pinfunction "CLK_6") (pintype "passive"))
      (node (ref "U1") (pin "34") (pinfunction "PB13/SPI2_SCK/I2S2_CK_34") (pintype "bidirectional"))
    )
    (net (code "36") (name "/SW1") (class "Default")
      (node (ref "C16") (pin "1") (pinfunction "1_1") (pintype "passive"))
      (node (ref "D10") (pin "1") (pinfunction "ANODE_1_1") (pintype "passive"))
      (node (ref "D10") (pin "2") (pinfunction "ANODE_2_2") (pintype "passive"))
      (node (ref "IC2") (pin "22") (pinfunction "SW1_22") (pintype "passive"))
      (node (ref "L2") (pin "1") (pinfunction "1_1") (pintype "passive"))
      (node (ref "Q10") (pin "5") (pinfunction "D_5") (pintype "passive"))
      (node (ref "Q10") (pin "6") (pinfunction "D_6") (pintype "passive"))
      (node (ref "Q10") (pin "7") (pinfunction "D_7") (pintype "passive"))
      (node (ref "Q10") (pin "8") (pinfunction "D_8") (pintype "passive"))
      (node (ref "Q8") (pin "1") (pinfunction "S_1") (pintype "passive"))
      (node (ref "Q8") (pin "2") (pinfunction "S_2") (pintype "passive"))
      (node (ref "Q8") (pin "3") (pinfunction "S_3") (pintype "passive"))
    )
    (net (code "37") (name "/SW2") (class "Default")
      (node (ref "C15") (pin "1") (pinfunction "1_1") (pintype "passive"))
      (node (ref "D11") (pin "3") (pinfunction "HEATSINK_3") (pintype "passive"))
      (node (ref "IC2") (pin "15") (pinfunction "SW2_15") (pintype "passive"))
      (node (ref "L2") (pin "2") (pinfunction "2_2") (pintype "passive"))
      (node (ref "Q7") (pin "1") (pinfunction "S_1") (pintype "passive"))
      (node (ref "Q7") (pin "2") (pinfunction "S_2") (pintype "passive"))
      (node (ref "Q7") (pin "3") (pinfunction "S_3") (pintype "passive"))
      (node (ref "Q9") (pin "5") (pinfunction "D_5") (pintype "passive"))
      (node (ref "Q9") (pin "6") (pinfunction "D_6") (pintype "passive"))
      (node (ref "Q9") (pin "7") (pinfunction "D_7") (pintype "passive"))
      (node (ref "Q9") (pin "8") (pinfunction "D_8") (pintype "passive"))
    )
    (net (code "38") (name "/SWCLK") (class "Default")
      (node (ref "JP2") (pin "3") (pinfunction "3_3") (pintype "passive"))
      (node (ref "U1") (pin "49") (pinfunction "PA14/JTCK/SWCLK_49") (pintype "bidirectional"))
    )
    (net (code "39") (name "/SWDIO") (class "Default")
      (node (ref "JP2") (pin "2") (pinfunction "2_2") (pintype "passive"))
      (node (ref "U1") (pin "46") (pinfunction "PA13/JTMS/SWDIO_46") (pintype "bidirectional"))
    )
    (net (code "40") (name "/TFT_BLK") (class "Default")
      (node (ref "JP3") (pin "21") (pinfunction "21_21") (pintype "passive"))
      (node (ref "U1") (pin "37") (pinfunction "SDIO_D6/I2S2_MCK/PC6_37") (pintype "bidirectional"))
    )
    (net (code "41") (name "/TFT_DC") (class "Default")
      (node (ref "JP3") (pin "26") (pinfunction "26_26") (pintype "passive"))
      (node (ref "U1") (pin "53") (pinfunction "PC12/SDIO_CK/USART5_TX_53") (pintype "bidirectional"))
    )
    (net (code "42") (name "/TFT_RES") (class "Default")
      (node (ref "JP3") (pin "23") (pinfunction "23_23") (pintype "passive"))
      (node (ref "U1") (pin "54") (pinfunction "PD2/SDIO_CMD/USART5_RX_54") (pintype "bidirectional"))
    )
    (net (code "43") (name "/TG1") (class "Default")
      (node (ref "IC2") (pin "23") (pinfunction "TG1_23") (pintype "passive"))
      (node (ref "Q8") (pin "4") (pinfunction "G_4") (pintype "passive"))
    )
    (net (code "44") (name "/TG2") (class "Default")
      (node (ref "IC2") (pin "14") (pinfunction "TG2_14") (pintype "passive"))
      (node (ref "Q7") (pin "4") (pinfunction "G_4") (pintype "passive"))
    )
    (net (code "45") (name "/U1_RX") (class "Default")
      (node (ref "U1") (pin "43") (pinfunction "PA10/USART1_RX_43") (pintype "bidirectional"))
      (node (ref "U1R") (pin "1") (pinfunction "1_1") (pintype "passive"))
      (node (ref "U3") (pin "2") (pinfunction "TxD_2") (pintype "passive"))
    )
    (net (code "46") (name "/U1_TX") (class "Default")
      (node (ref "U1") (pin "42") (pinfunction "PA9/USART1_TX_42") (pintype "bidirectional"))
      (node (ref "U1T") (pin "1") (pinfunction "1_1") (pintype "passive"))
      (node (ref "U3") (pin "3") (pinfunction "RxD_3") (pintype "passive"))
    )
    (net (code "47") (name "/U3_RX") (class "Default")
      (node (ref "JP3") (pin "25") (pinfunction "25_25") (pintype "passive"))
      (node (ref "U1") (pin "52") (pinfunction "PC11/SDIO_D3/USART4_RX_52") (pintype "bidirectional"))
      (node (ref "U3R") (pin "1") (pinfunction "1_1") (pintype "passive"))
    )
    (net (code "48") (name "/U3_TX") (class "Default")
      (node (ref "JP3") (pin "28") (pinfunction "28_28") (pintype "passive"))
      (node (ref "U1") (pin "51") (pinfunction "PC10/SDIO_D2/USART4_TX_51") (pintype "bidirectional"))
      (node (ref "U3T") (pin "1") (pinfunction "1_1") (pintype "passive"))
    )
    (net (code "49") (name "3V3") (class "Default")
      (node (ref "BAT_TEMP") (pin "1") (pinfunction "1_1") (pintype "passive"))
      (node (ref "C18") (pin "2") (pinfunction "2_2") (pintype "passive"))
      (node (ref "C2") (pin "2") (pinfunction "2_2") (pintype "passive"))
      (node (ref "C21") (pin "1") (pinfunction "1_1") (pintype "passive"))
      (node (ref "C36") (pin "1") (pinfunction "1_1") (pintype "passive"))
      (node (ref "C39") (pin "1") (pinfunction "1_1") (pintype "passive"))
      (node (ref "C45") (pin "2") (pinfunction "2_2") (pintype "passive"))
      (node (ref "C47") (pin "2") (pinfunction "2_2") (pintype "passive"))
      (node (ref "C7") (pin "2") (pinfunction "2_2") (pintype "passive"))
      (node (ref "IC1") (pin "6") (pinfunction "VS_6") (pintype "passive"))
      (node (ref "IC10") (pin "8") (pinfunction "VCC_8") (pintype "power_in"))
      (node (ref "IC11") (pin "3") (pinfunction "~{WP}_3") (pintype "passive"))
      (node (ref "IC11") (pin "7") (pinfunction "~{HOLD}_7") (pintype "passive"))
      (node (ref "IC11") (pin "8") (pinfunction "VCC_8") (pintype "passive"))
      (node (ref "IC4") (pin "8") (pinfunction "V+_8") (pintype "power_in"))
      (node (ref "IC9") (pin "8") (pinfunction "VCC_8") (pintype "passive"))
      (node (ref "JP2") (pin "1") (pinfunction "1_1") (pintype "passive"))
      (node (ref "Q5") (pin "2") (pinfunction "E_2") (pintype "passive"))
      (node (ref "R1") (pin "2") (pinfunction "2_2") (pintype "passive"))
      (node (ref "R15") (pin "2") (pinfunction "2_2") (pintype "passive"))
      (node (ref "R16") (pin "2") (pinfunction "2_2") (pintype "passive"))
      (node (ref "R29") (pin "2") (pinfunction "2_2") (pintype "passive"))
      (node (ref "R31") (pin "2") (pinfunction "2_2") (pintype "passive"))
      (node (ref "U2") (pin "11") (pinfunction "SEL_11") (pintype "passive"))
      (node (ref "U5") (pin "5") (pinfunction "V+_5") (pintype "passive"))
      (node (ref "V1") (pin "2") (pinfunction "Vout_2") (pintype "passive"))
    )
    (net (code "50") (name "3V3_MCU") (class "Default")
      (node (ref "C25") (pin "2") (pinfunction "2_2") (pintype "passive"))
      (node (ref "C26") (pin "2") (pinfunction "2_2") (pintype "passive"))
      (node (ref "C27") (pin "2") (pinfunction "2_2") (pintype "passive"))
      (node (ref "C28") (pin "2") (pinfunction "2_2") (pintype "passive"))
      (node (ref "C54") (pin "2") (pinfunction "2_2") (pintype "passive"))
      (node (ref "L4") (pin "1") (pinfunction "1_1") (pintype "passive"))
      (node (ref "R18") (pin "1") (pinfunction "1_1") (pintype "passive"))
      (node (ref "U1") (pin "1") (pinfunction "VBAT_1") (pintype "power_in"))
      (node (ref "U1") (pin "19") (pinfunction "VDD_4_19") (pintype "power_in"))
      (node (ref "U1") (pin "32") (pinfunction "VDD_1_32") (pintype "power_in"))
      (node (ref "U1") (pin "48") (pinfunction "VDD_2_48") (pintype "power_in"))
      (node (ref "U1") (pin "64") (pinfunction "VDD_3_64") (pintype "power_in"))
      (node (ref "U6") (pin "5") (pinfunction "VOUT_5") (pintype "passive"))
    )
    (net (code "51") (name "5V") (class "Default")
      (node (ref "C37") (pin "1") (pinfunction "1_1") (pintype "passive"))
      (node (ref "C46") (pin "2") (pinfunction "2_2") (pintype "passive"))
      (node (ref "C55") (pin "2") (pinfunction "2_2") (pintype "passive"))
      (node (ref "D1") (pin "2") (pinfunction "K_2") (pintype "passive"))
      (node (ref "E7") (pin "1") (pinfunction "A_1") (pintype "passive"))
      (node (ref "FAN") (pin "1") (pinfunction "1_1") (pintype "passive"))
      (node (ref "IC3") (pin "3") (pinfunction "FEEDBACK_3") (pintype "passive"))
      (node (ref "JP3") (pin "34") (pinfunction "34_34") (pintype "passive"))
      (node (ref "JP3") (pin "36") (pinfunction "36_36") (pintype "passive"))
      (node (ref "L3") (pin "2") (pinfunction "2_2") (pintype "passive"))
      (node (ref "U6") (pin "1") (pinfunction "VIN_1") (pintype "passive"))
      (node (ref "U6") (pin "3") (pinfunction "EN_3") (pintype "passive"))
      (node (ref "V1") (pin "3") (pinfunction "Vin_3") (pintype "passive"))
    )
    (net (code "52") (name "AGND") (class "Default")
      (node (ref "B2") (pin "2") (pinfunction "V-_2") (pintype "passive"))
      (node (ref "C1") (pin "1") (pinfunction "1_1") (pintype "passive"))
      (node (ref "C11") (pin "2") (pinfunction "2_2") (pintype "passive"))
      (node (ref "C12") (pin "1") (pinfunction "1_1") (pintype "passive"))
      (node (ref "C13") (pin "1") (pinfunction "1_1") (pintype "passive"))
      (node (ref "C14") (pin "1") (pinfunction "1_1") (pintype "passive"))
      (node (ref "C18") (pin "1") (pinfunction "1_1") (pintype "passive"))
      (node (ref "C2") (pin "1") (pinfunction "1_1") (pintype "passive"))
      (node (ref "C20") (pin "1") (pinfunction "1_1") (pintype "passive"))
      (node (ref "C21") (pin "2") (pinfunction "2_2") (pintype "passive"))
      (node (ref "C23") (pin "1") (pinfunction "1_1") (pintype "passive"))
      (node (ref "C29") (pin "2") (pinfunction "2_2") (pintype "passive"))
      (node (ref "C3") (pin "2") (pinfunction "2_2") (pintype "passive"))
      (node (ref "C30") (pin "2") (pinfunction "2_2") (pintype "passive"))
      (node (ref "C31") (pin "2") (pinfunction "2_2") (pintype "passive"))
      (node (ref "C32") (pin "1") (pinfunction "1_1") (pintype "passive"))
      (node (ref "C34") (pin "2") (pinfunction "2_2") (pintype "passive"))
      (node (ref "C35") (pin "2") (pinfunction "2_2") (pintype "passive"))
      (node (ref "C36") (pin "2") (pinfunction "2_2") (pintype "passive"))
      (node (ref "C37") (pin "2") (pinfunction "2_2") (pintype "passive"))
      (node (ref "C38") (pin "2") (pinfunction "2_2") (pintype "passive"))
      (node (ref "C39") (pin "2") (pinfunction "2_2") (pintype "passive"))
      (node (ref "C4") (pin "1") (pinfunction "1_1") (pintype "passive"))
      (node (ref "C45") (pin "1") (pinfunction "1_1") (pintype "passive"))
      (node (ref "C46") (pin "1") (pinfunction "1_1") (pintype "passive"))
      (node (ref "C47") (pin "1") (pinfunction "1_1") (pintype "passive"))
      (node (ref "C5") (pin "1") (pinfunction "1_1") (pintype "passive"))
      (node (ref "C53") (pin "1") (pinfunction "1_1") (pintype "passive"))
      (node (ref "C54") (pin "1") (pinfunction "1_1") (pintype "passive"))
      (node (ref "C55") (pin "1") (pinfunction "1_1") (pintype "passive"))
      (node (ref "C56") (pin "1") (pinfunction "1_1") (pintype "passive"))
      (node (ref "C7") (pin "1") (pinfunction "1_1") (pintype "passive"))
      (node (ref "C8") (pin "2") (pinfunction "2_2") (pintype "passive"))
      (node (ref "C9") (pin "1") (pinfunction "1_1") (pintype "passive"))
      (node (ref "CON1") (pin "2") (pintype "power_in"))
      (node (ref "D7") (pin "1") (pinfunction "A_1") (pintype "passive"))
      (node (ref "E1") (pin "2") (pinfunction "K_2") (pintype "passive"))
      (node (ref "E2") (pin "2") (pinfunction "K_2") (pintype "passive"))
      (node (ref "E3") (pin "2") (pinfunction "K_2") (pintype "passive"))
      (node (ref "E4") (pin "2") (pinfunction "K_2") (pintype "passive"))
      (node (ref "E5") (pin "2") (pinfunction "K_2") (pintype "passive"))
      (node (ref "E6") (pin "2") (pinfunction "K_2") (pintype "passive"))
      (node (ref "E7") (pin "2") (pinfunction "K_2") (pintype "passive"))
      (node (ref "E8") (pin "2") (pinfunction "K_2") (pintype "passive"))
      (node (ref "E9") (pin "2") (pinfunction "K_2") (pintype "passive"))
      (node (ref "EK1") (pin "1") (pinfunction "1_1") (pintype "passive"))
      (node (ref "EK2") (pin "1") (pinfunction "1_1") (pintype "passive"))
      (node (ref "EK3") (pin "2") (pinfunction "2_2") (pintype "passive"))
      (node (ref "EK4") (pin "2") (pinfunction "2_2") (pintype "passive"))
      (node (ref "IC1") (pin "1") (pinfunction "A1_1") (pintype "passive"))
      (node (ref "IC1") (pin "2") (pinfunction "A0_2") (pintype "passive"))
      (node (ref "IC1") (pin "7") (pinfunction "GND_7") (pintype "passive"))
      (node (ref "IC1") (pin "9") (pinfunction "IN-_9") (pintype "passive"))
      (node (ref "IC10") (pin "1") (pinfunction "A0_1") (pintype "input"))
      (node (ref "IC10") (pin "2") (pinfunction "A1_2") (pintype "input"))
      (node (ref "IC10") (pin "3") (pinfunction "A2_3") (pintype "input"))
      (node (ref "IC10") (pin "4") (pinfunction "GND_4") (pintype "passive"))
      (node (ref "IC10") (pin "7") (pinfunction "WP_7") (pintype "passive"))
      (node (ref "IC11") (pin "4") (pinfunction "GND_4") (pintype "passive"))
      (node (ref "IC2") (pin "11") (pinfunction "PLLIN_11") (pintype "passive"))
      (node (ref "IC2") (pin "17") (pinfunction "PGND_17") (pintype "passive"))
      (node (ref "IC2") (pin "20") (pinfunction "EXTVCC_20") (pintype "passive"))
      (node (ref "IC2") (pin "7") (pinfunction "SGND_7") (pintype "passive"))
      (node (ref "IC2") (pin "9") (pinfunction "FCB_9") (pintype "passive"))
      (node (ref "IC3") (pin "4") (pinfunction "ON/OFF_4") (pintype "passive"))
      (node (ref "IC3") (pin "5") (pinfunction "GND_1_5") (pintype "passive"))
      (node (ref "IC3") (pin "6") (pinfunction "GND_2_6") (pintype "passive"))
      (node (ref "IC3") (pin "7") (pinfunction "GND_3_7") (pintype "passive"))
      (node (ref "IC3") (pin "8") (pinfunction "GND_4_8") (pintype "passive"))
      (node (ref "IC4") (pin "4") (pinfunction "V-_4") (pintype "power_in"))
      (node (ref "IC9") (pin "4") (pinfunction "GND_4") (pintype "passive"))
      (node (ref "JP2") (pin "4") (pinfunction "4_4") (pintype "passive"))
      (node (ref "JP3") (pin "33") (pinfunction "33_33") (pintype "passive"))
      (node (ref "JP3") (pin "35") (pinfunction "35_35") (pintype "passive"))
      (node (ref "NTC1") (pin "1") (pinfunction "1_1") (pintype "passive"))
      (node (ref "NTC2") (pin "1") (pinfunction "1_1") (pintype "passive"))
      (node (ref "Q14") (pin "2") (pinfunction "S_2") (pintype "passive"))
      (node (ref "Q19") (pin "2") (pinfunction "E_2") (pintype "passive"))
      (node (ref "Q20") (pin "2") (pinfunction "E_2") (pintype "passive"))
      (node (ref "Q4") (pin "1") (pinfunction "S_1") (pintype "passive"))
      (node (ref "Q4") (pin "2") (pinfunction "S_2") (pintype "passive"))
      (node (ref "Q4") (pin "3") (pinfunction "S_3") (pintype "passive"))
      (node (ref "Q6") (pin "2") (pinfunction "E_2") (pintype "passive"))
      (node (ref "R13") (pin "1") (pinfunction "1_1") (pintype "passive"))
      (node (ref "R17") (pin "1") (pinfunction "1_1") (pintype "passive"))
      (node (ref "R22") (pin "2") (pinfunction "2_2") (pintype "passive"))
      (node (ref "R26") (pin "1") (pinfunction "1_1") (pintype "passive"))
      (node (ref "R27") (pin "1") (pinfunction "1_1") (pintype "passive"))
      (node (ref "R3") (pin "2") (pinfunction "2_2") (pintype "passive"))
      (node (ref "R30") (pin "1") (pinfunction "1_1") (pintype "passive"))
      (node (ref "R32") (pin "2") (pinfunction "2_2") (pintype "passive"))
      (node (ref "R33") (pin "1") (pinfunction "1_1") (pintype "passive"))
      (node (ref "R47") (pin "1") (pinfunction "1_1") (pintype "passive"))
      (node (ref "R52") (pin "1") (pinfunction "1_1") (pintype "passive"))
      (node (ref "R54") (pin "2") (pinfunction "2_2") (pintype "passive"))
      (node (ref "R58") (pin "1") (pinfunction "1_1") (pintype "passive"))
      (node (ref "R63") (pin "2") (pinfunction "2_2") (pintype "passive"))
      (node (ref "R64") (pin "2") (pinfunction "2_2") (pintype "passive"))
      (node (ref "R66") (pin "2") (pinfunction "2_2") (pintype "passive"))
      (node (ref "R67") (pin "2") (pinfunction "2_2") (pintype "passive"))
      (node (ref "R68") (pin "2") (pinfunction "2_2") (pintype "passive"))
      (node (ref "R72") (pin "1") (pinfunction "1_1") (pintype "passive"))
      (node (ref "R73") (pin "2") (pinfunction "2_2") (pintype "passive"))
      (node (ref "R74") (pin "1") (pinfunction "1_1") (pintype "passive"))
      (node (ref "R9") (pin "2") (pinfunction "2_2") (pintype "passive"))
      (node (ref "TYPEC1") (pin "0") (pinfunction "SHIBLD_0") (pintype "passive"))
      (node (ref "TYPEC1") (pin "A1") (pinfunction "GND_A1") (pintype "passive"))
      (node (ref "TYPEC1") (pin "A12") (pinfunction "GND_A12") (pintype "passive"))
      (node (ref "TYPEC1") (pin "B1") (pinfunction "GND_B1") (pintype "passive"))
      (node (ref "TYPEC1") (pin "B12") (pinfunction "GND_B12") (pintype "passive"))
      (node (ref "TYPEC2") (pin "0") (pinfunction "SHIBLD_0") (pintype "passive"))
      (node (ref "TYPEC2") (pin "A1") (pinfunction "GND_A1") (pintype "passive"))
      (node (ref "TYPEC2") (pin "A12") (pinfunction "GND_A12") (pintype "passive"))
      (node (ref "TYPEC2") (pin "B1") (pinfunction "GND_B1") (pintype "passive"))
      (node (ref "TYPEC2") (pin "B12") (pinfunction "GND_B12") (pintype "passive"))
      (node (ref "U1") (pin "12") (pinfunction "VSSA_12") (pintype "power_in"))
      (node (ref "U2") (pin "5") (pinfunction "GND_5") (pintype "passive"))
      (node (ref "U3") (pin "1") (pinfunction "GND_1") (pintype "passive"))
      (node (ref "U4") (pin "12") (pinfunction "AGND_12") (pintype "passive"))
      (node (ref "U4") (pin "13") (pinfunction "ADIN_13") (pintype "passive"))
      (node (ref "U4") (pin "25") (pinfunction "PGND_25") (pintype "passive"))
      (node (ref "U4") (pin "33") (pinfunction "PGND_33") (pintype "passive"))
      (node (ref "U4") (pin "7") (pinfunction "/CE_7") (pintype "passive"))
      (node (ref "U5") (pin "2") (pinfunction "V-_2") (pintype "passive"))
      (node (ref "U6") (pin "2") (pinfunction "GND_2") (pintype "passive"))
      (node (ref "V1") (pin "1") (pinfunction "GND_1") (pintype "passive"))
    )
    (net (code "53") (name "BAT+") (class "Default")
      (node (ref "C14") (pin "2") (pinfunction "2_2") (pintype "passive"))
      (node (ref "D6") (pin "1") (pinfunction "A_1") (pintype "passive"))
      (node (ref "E2") (pin "1") (pinfunction "A_1") (pintype "passive"))
      (node (ref "EK3") (pin "1") (pinfunction "1_1") (pintype "passive"))
      (node (ref "Q11") (pin "3") (pinfunction "S_3") (pintype "passive"))
      (node (ref "Q2") (pin "2") (pinfunction "D_2") (pintype "passive"))
      (node (ref "R38") (pin "1") (pinfunction "1_1") (pintype "passive"))
      (node (ref "R39") (pin "1") (pinfunction "1_1") (pintype "passive"))
      (node (ref "R7") (pin "2") (pinfunction "2_2") (pintype "passive"))
      (node (ref "U4") (pin "18") (pinfunction "VBATS_18") (pintype "passive"))
      (node (ref "U4") (pin "19") (pinfunction "SNS2N_19") (pintype "passive"))
      (node (ref "U4") (pin "21") (pinfunction "VBAT_21") (pintype "passive"))
    )
    (net (code "54") (name "BAT1") (class "Default")
      (node (ref "R59") (pin "2") (pinfunction "2_2") (pintype "passive"))
      (node (ref "R66") (pin "1") (pinfunction "1_1") (pintype "passive"))
      (node (ref "U1") (pin "27") (pinfunction "ADC12_IN9/PB1_27") (pintype "bidirectional"))
    )
    (net (code "55") (name "BAT1+") (class "Default")
      (node (ref "B1") (pin "1") (pinfunction "+_1") (pintype "passive"))
      (node (ref "C42") (pin "1") (pinfunction "1_1") (pintype "passive"))
      (node (ref "C43") (pin "1") (pinfunction "1_1") (pintype "passive"))
      (node (ref "C44") (pin "1") (pinfunction "1_1") (pintype "passive"))
      (node (ref "C48") (pin "1") (pinfunction "1_1") (pintype "passive"))
      (node (ref "IC6") (pin "16") (pinfunction "VDD_16") (pintype "passive"))
      (node (ref "Q12") (pin "3") (pinfunction "S_3") (pintype "passive"))
      (node (ref "R35") (pin "1") (pinfunction "1_1") (pintype "passive"))
      (node (ref "R36") (pin "1") (pinfunction "1_1") (pintype "passive"))
      (node (ref "R42") (pin "1") (pinfunction "1_1") (pintype "passive"))
      (node (ref "R59") (pin "1") (pinfunction "1_1") (pintype "passive"))
    )
    (net (code "56") (name "BAT2") (class "Default")
      (node (ref "R60") (pin "2") (pinfunction "2_2") (pintype "passive"))
      (node (ref "R67") (pin "1") (pinfunction "1_1") (pintype "passive"))
      (node (ref "U1") (pin "26") (pinfunction "ADC12_IN8/PB0_26") (pintype "bidirectional"))
    )
    (net (code "57") (name "BAT2+") (class "Default")
      (node (ref "B1") (pin "2") (pinfunction "-_2") (pintype "passive"))
      (node (ref "B1") (pin "4") (pinfunction "+_4") (pintype "passive"))
      (node (ref "C41") (pin "1") (pinfunction "1_1") (pintype "passive"))
      (node (ref "IC5") (pin "3") (pinfunction "VSS_3") (pintype "passive"))
      (node (ref "Q13") (pin "2") (pinfunction "S_2") (pintype "passive"))
      (node (ref "R43") (pin "1") (pinfunction "1_1") (pintype "passive"))
      (node (ref "R45") (pin "1") (pinfunction "1_1") (pintype "passive"))
      (node (ref "R49") (pin "1") (pinfunction "1_1") (pintype "passive"))
      (node (ref "R60") (pin "1") (pinfunction "1_1") (pintype "passive"))
    )
    (net (code "58") (name "BAT3") (class "Default")
      (node (ref "R61") (pin "2") (pinfunction "2_2") (pintype "passive"))
      (node (ref "R68") (pin "1") (pinfunction "1_1") (pintype "passive"))
      (node (ref "U1") (pin "23") (pinfunction "ADC12_IN7/SPI1_MOSI/PA7_23") (pintype "bidirectional"))
    )
    (net (code "59") (name "BAT3+") (class "Default")
      (node (ref "B1") (pin "3") (pinfunction "-_3") (pintype "passive"))
      (node (ref "B1") (pin "5") (pinfunction "+_5") (pintype "passive"))
      (node (ref "C52") (pin "1") (pinfunction "1_1") (pintype "passive"))
      (node (ref "IC7") (pin "3") (pinfunction "VSS_3") (pintype "passive"))
      (node (ref "Q15") (pin "2") (pinfunction "S_2") (pintype "passive"))
      (node (ref "R44") (pin "1") (pinfunction "1_1") (pintype "passive"))
      (node (ref "R55") (pin "1") (pinfunction "1_1") (pintype "passive"))
      (node (ref "R61") (pin "1") (pinfunction "1_1") (pintype "passive"))
      (node (ref "R62") (pin "1") (pinfunction "1_1") (pintype "passive"))
    )
    (net (code "60") (name "CC1") (class "Default")
      (node (ref "R3") (pin "1") (pinfunction "1_1") (pintype "passive"))
      (node (ref "TYPEC2") (pin "A5") (pinfunction "CC1_A5") (pintype "passive"))
      (node (ref "U2") (pin "13") (pinfunction "CC1_13") (pintype "passive"))
    )
    (net (code "61") (name "CC2") (class "Default")
      (node (ref "R9") (pin "1") (pinfunction "1_1") (pintype "passive"))
      (node (ref "TYPEC2") (pin "B5") (pinfunction "CC2_B5") (pintype "passive"))
      (node (ref "U2") (pin "12") (pinfunction "CC2_12") (pintype "passive"))
    )
    (net (code "62") (name "DAC_I") (class "Default")
      (node (ref "DAC_I") (pin "1") (pinfunction "1_1") (pintype "passive"))
      (node (ref "R37") (pin "1") (pinfunction "1_1") (pintype "passive"))
      (node (ref "U1") (pin "21") (pinfunction "DAC_OUT2/SPI1_SCK/PA5_21") (pintype "bidirectional"))
    )
    (net (code "63") (name "DAC_V") (class "Default")
      (node (ref "DAC_V") (pin "1") (pinfunction "1_1") (pintype "passive"))
      (node (ref "R50") (pin "1") (pinfunction "1_1") (pintype "passive"))
      (node (ref "U1") (pin "20") (pinfunction "DAC_OUT1/SPI1_NSS/PA4_20") (pintype "bidirectional"))
    )
    (net (code "64") (name "DGND") (class "Default")
      (node (ref "C17") (pin "1") (pinfunction "1_1") (pintype "passive"))
      (node (ref "C19") (pin "2") (pinfunction "2_2") (pintype "passive"))
      (node (ref "C22") (pin "1") (pinfunction "1_1") (pintype "passive"))
      (node (ref "C25") (pin "1") (pinfunction "1_1") (pintype "passive"))
      (node (ref "C26") (pin "1") (pinfunction "1_1") (pintype "passive"))
      (node (ref "C27") (pin "1") (pinfunction "1_1") (pintype "passive"))
      (node (ref "C28") (pin "1") (pinfunction "1_1") (pintype "passive"))
      (node (ref "C33") (pin "1") (pinfunction "1_1") (pintype "passive"))
      (node (ref "R19") (pin "1") (pinfunction "1_1") (pintype "passive"))
      (node (ref "R26") (pin "2") (pinfunction "2_2") (pintype "passive"))
      (node (ref "U1") (pin "18") (pinfunction "VSS_4_18") (pintype "power_in"))
      (node (ref "U1") (pin "31") (pinfunction "VSS_1_31") (pintype "passive"))
      (node (ref "U1") (pin "47") (pinfunction "VSS_2_47") (pintype "passive"))
      (node (ref "U1") (pin "63") (pinfunction "VSS_3_63") (pintype "power_in"))
    )
    (net (code "65") (name "FAN") (class "Default")
      (node (ref "R40") (pin "2") (pinfunction "2_2") (pintype "passive"))
      (node (ref "U1") (pin "17") (pinfunction "USART2_RX/PA3_17") (pintype "bidirectional"))
    )
    (net (code "66") (name "FB") (class "Default")
      (node (ref "D8") (pin "2") (pinfunction "K_2") (pintype "passive"))
      (node (ref "D9") (pin "2") (pinfunction "K_2") (pintype "passive"))
      (node (ref "IC2") (pin "6") (pinfunction "VOSENSE_6") (pintype "passive"))
      (node (ref "R25") (pin "1") (pinfunction "1_1") (pintype "passive"))
      (node (ref "R27") (pin "2") (pinfunction "2_2") (pintype "passive"))
    )
    (net (code "67") (name "INTVCC") (class "Default")
      (node (ref "C32") (pin "2") (pinfunction "2_2") (pintype "passive"))
      (node (ref "D3") (pin "1") (pinfunction "A_1") (pintype "passive"))
      (node (ref "D4") (pin "1") (pinfunction "A_1") (pintype "passive"))
      (node (ref "IC2") (pin "19") (pinfunction "INTVCC_19") (pintype "passive"))
      (node (ref "R24") (pin "2") (pinfunction "2_2") (pintype "passive"))
    )
    (net (code "68") (name "MOS_BAT") (class "Default")
      (node (ref "R12") (pin "1") (pinfunction "1_1") (pintype "passive"))
      (node (ref "U1") (pin "28") (pinfunction "BOOT1/PB2_28") (pintype "bidirectional"))
    )
    (net (code "69") (name "MOS_IN") (class "Default")
      (node (ref "R70") (pin "1") (pinfunction "1_1") (pintype "passive"))
      (node (ref "U1") (pin "25") (pinfunction "ADC12_IN15/PC5_25") (pintype "bidirectional"))
    )
    (net (code "70") (name "MOS_OUT") (class "Default")
      (node (ref "R71") (pin "1") (pinfunction "1_1") (pintype "passive"))
      (node (ref "U1") (pin "24") (pinfunction "ADC12_IN14/PC4_24") (pintype "bidirectional"))
    )
    (net (code "71") (name "Net-(B2-V+)") (class "Default")
      (node (ref "B2") (pin "1") (pinfunction "V+_1") (pintype "passive"))
      (node (ref "IC9") (pin "3") (pinfunction "VBAT_3") (pintype "passive"))
    )
    (net (code "72") (name "Net-(C8-Pad1)") (class "Default")
      (node (ref "C8") (pin "1") (pinfunction "1_1") (pintype "passive"))
      (node (ref "R65") (pin "1") (pinfunction "1_1") (pintype "passive"))
    )
    (net (code "73") (name "Net-(C29-Pad1)") (class "Default")
      (node (ref "C29") (pin "1") (pinfunction "1_1") (pintype "passive"))
      (node (ref "R23") (pin "2") (pinfunction "2_2") (pintype "passive"))
    )
    (net (code "74") (name "Net-(D2-K)") (class "Default")
      (node (ref "D2") (pin "2") (pinfunction "K_2") (pintype "passive"))
      (node (ref "Q3") (pin "3") (pinfunction "C_3") (pintype "passive"))
      (node (ref "R1") (pin "1") (pinfunction "1_1") (pintype "passive"))
    )
    (net (code "75") (name "Net-(D5-K)") (class "Default")
      (node (ref "C1") (pin "2") (pinfunction "2_2") (pintype "passive"))
      (node (ref "D5") (pin "2") (pinfunction "K_2") (pintype "passive"))
      (node (ref "D6") (pin "2") (pinfunction "K_2") (pintype "passive"))
      (node (ref "IC3") (pin "1") (pinfunction "VIN_1") (pintype "passive"))
    )
    (net (code "76") (name "Net-(D7-K)") (class "Default")
      (node (ref "D7") (pin "2") (pinfunction "K_2") (pintype "passive"))
      (node (ref "IC3") (pin "2") (pinfunction "OUTPUT_2") (pintype "passive"))
      (node (ref "L3") (pin "1") (pinfunction "1_1") (pintype "passive"))
    )
    (net (code "77") (name "Net-(D8-A)") (class "Default")
      (node (ref "C40") (pin "1") (pinfunction "1_1") (pintype "passive"))
      (node (ref "D8") (pin "1") (pinfunction "A_1") (pintype "passive"))
      (node (ref "IC4") (pin "1") (pinfunction "OUT_1") (pintype "output"))
    )
    (net (code "78") (name "Net-(D9-A)") (class "Default")
      (node (ref "C51") (pin "1") (pinfunction "1_1") (pintype "passive"))
      (node (ref "D9") (pin "1") (pinfunction "A_1") (pintype "passive"))
      (node (ref "IC4") (pin "7") (pinfunction "OUT_7") (pintype "output"))
    )
    (net (code "79") (name "Net-(DZ1-A)") (class "Default")
      (node (ref "DZ1") (pin "1") (pinfunction "A_1") (pintype "passive"))
      (node (ref "Q17") (pin "1") (pinfunction "G_1") (pintype "passive"))
      (node (ref "Q19") (pin "3") (pinfunction "C_3") (pintype "passive"))
      (node (ref "R14") (pin "1") (pinfunction "1_1") (pintype "passive"))
    )
    (net (code "80") (name "Net-(DZ2-A)") (class "Default")
      (node (ref "DZ2") (pin "1") (pinfunction "A_1") (pintype "passive"))
      (node (ref "Q18") (pin "1") (pinfunction "G_1") (pintype "passive"))
      (node (ref "Q20") (pin "3") (pinfunction "C_3") (pintype "passive"))
      (node (ref "R69") (pin "1") (pinfunction "1_1") (pintype "passive"))
    )
    (net (code "81") (name "Net-(IC2-ITH)") (class "Default")
      (node (ref "C30") (pin "1") (pinfunction "1_1") (pintype "passive"))
      (node (ref "IC2") (pin "5") (pinfunction "ITH_5") (pintype "passive"))
      (node (ref "R23") (pin "1") (pinfunction "1_1") (pintype "passive"))
    )
    (net (code "82") (name "Net-(IC2-PLLFLTR)") (class "Default")
      (node (ref "IC2") (pin "10") (pinfunction "PLLFLTR_10") (pintype "passive"))
      (node (ref "R24") (pin "1") (pinfunction "1_1") (pintype "passive"))
    )
    (net (code "83") (name "Net-(IC2-SENSE+)") (class "Default")
      (node (ref "C24") (pin "2") (pinfunction "2_2") (pintype "passive"))
      (node (ref "IC2") (pin "3") (pinfunction "SENSE+_3") (pintype "passive"))
      (node (ref "R20") (pin "1") (pinfunction "1_1") (pintype "passive"))
    )
    (net (code "84") (name "Net-(IC2-SENSE-)") (class "Default")
      (node (ref "C24") (pin "1") (pinfunction "1_1") (pintype "passive"))
      (node (ref "IC2") (pin "4") (pinfunction "SENSE-_4") (pintype "passive"))
      (node (ref "R22") (pin "1") (pinfunction "1_1") (pintype "passive"))
    )
    (net (code "85") (name "Net-(IC2-SS)") (class "Default")
      (node (ref "C23") (pin "2") (pinfunction "2_2") (pintype "passive"))
      (node (ref "IC2") (pin "2") (pinfunction "SS_2") (pintype "passive"))
    )
    (net (code "86") (name "Net-(IC2-STBYMD)") (class "Default")
      (node (ref "C34") (pin "1") (pinfunction "1_1") (pintype "passive"))
      (node (ref "IC2") (pin "12") (pinfunction "STBYMD_12") (pintype "passive"))
    )
    (net (code "87") (name "Net-(IC2-VIN)") (class "Default")
      (node (ref "C31") (pin "1") (pinfunction "1_1") (pintype "passive"))
      (node (ref "IC2") (pin "21") (pinfunction "VIN_21") (pintype "passive"))
      (node (ref "R21") (pin "2") (pinfunction "2_2") (pintype "passive"))
    )
    (net (code "88") (name "Net-(IC4A-IN+)") (class "Default")
      (node (ref "IC4") (pin "3") (pinfunction "IN+_3") (pintype "input"))
      (node (ref "R34") (pin "2") (pinfunction "2_2") (pintype "passive"))
      (node (ref "U5") (pin "1") (pinfunction "OUT_1") (pintype "passive"))
    )
    (net (code "89") (name "Net-(IC4A-IN-)") (class "Default")
      (node (ref "C40") (pin "2") (pinfunction "2_2") (pintype "passive"))
      (node (ref "IC4") (pin "2") (pinfunction "IN-_2") (pintype "input"))
      (node (ref "R37") (pin "2") (pinfunction "2_2") (pintype "passive"))
    )
    (net (code "90") (name "Net-(IC4B-IN+)") (class "Default")
      (node (ref "IC4") (pin "5") (pinfunction "IN+_5") (pintype "input"))
      (node (ref "R46") (pin "1") (pinfunction "1_1") (pintype "passive"))
      (node (ref "R52") (pin "2") (pinfunction "2_2") (pintype "passive"))
    )
    (net (code "91") (name "Net-(IC4B-IN-)") (class "Default")
      (node (ref "C51") (pin "2") (pinfunction "2_2") (pintype "passive"))
      (node (ref "IC4") (pin "6") (pinfunction "IN-_6") (pintype "input"))
      (node (ref "R50") (pin "2") (pinfunction "2_2") (pintype "passive"))
    )
    (net (code "92") (name "Net-(IC5-OUT)") (class "Default")
      (node (ref "IC5") (pin "6") (pinfunction "OUT_6") (pintype "passive"))
      (node (ref "Q13") (pin "1") (pinfunction "G_1") (pintype "passive"))
    )
    (net (code "93") (name "Net-(IC5-VDD)") (class "Default")
      (node (ref "C41") (pin "2") (pinfunction "2_2") (pintype "passive"))
      (node (ref "IC5") (pin "2") (pinfunction "VDD_2") (pintype "passive"))
      (node (ref "R36") (pin "2") (pinfunction "2_2") (pintype "passive"))
    )
    (net (code "94") (name "Net-(IC6-CCT)") (class "Default")
      (node (ref "C50") (pin "1") (pinfunction "1_1") (pintype "passive"))
      (node (ref "IC6") (pin "6") (pinfunction "CCT_6") (pintype "passive"))
    )
    (net (code "95") (name "Net-(IC6-CDT)") (class "Default")
      (node (ref "C49") (pin "1") (pinfunction "1_1") (pintype "passive"))
      (node (ref "IC6") (pin "5") (pinfunction "CDT_5") (pintype "passive"))
    )
    (net (code "96") (name "Net-(IC6-COP)") (class "Default")
      (node (ref "IC6") (pin "1") (pinfunction "COP_1") (pintype "passive"))
      (node (ref "Q11") (pin "1") (pinfunction "G_1") (pintype "passive"))
      (node (ref "R39") (pin "2") (pinfunction "2_2") (pintype "passive"))
    )
    (net (code "97") (name "Net-(IC6-CTL)") (class "Default")
      (node (ref "IC6") (pin "11") (pinfunction "CTL_11") (pintype "passive"))
      (node (ref "R48") (pin "2") (pinfunction "2_2") (pintype "passive"))
    )
    (net (code "98") (name "Net-(IC6-DOP)") (class "Default")
      (node (ref "IC6") (pin "3") (pinfunction "DOP_3") (pintype "passive"))
      (node (ref "R41") (pin "1") (pinfunction "1_1") (pintype "passive"))
    )
    (net (code "99") (name "Net-(IC6-SEL)") (class "Default")
      (node (ref "IC6") (pin "10") (pinfunction "SEL_10") (pintype "passive"))
      (node (ref "R51") (pin "2") (pinfunction "2_2") (pintype "passive"))
    )
    (net (code "100") (name "Net-(IC6-VC1)") (class "Default")
      (node (ref "C42") (pin "2") (pinfunction "2_2") (pintype "passive"))
      (node (ref "IC6") (pin "15") (pinfunction "VC1_15") (pintype "passive"))
      (node (ref "R42") (pin "2") (pinfunction "2_2") (pintype "passive"))
    )
    (net (code "101") (name "Net-(IC6-VC2)") (class "Default")
      (node (ref "C43") (pin "2") (pinfunction "2_2") (pintype "passive"))
      (node (ref "IC6") (pin "14") (pinfunction "VC2_14") (pintype "passive"))
      (node (ref "R43") (pin "2") (pinfunction "2_2") (pintype "passive"))
    )
    (net (code "102") (name "Net-(IC6-VC3)") (class "Default")
      (node (ref "C44") (pin "2") (pinfunction "2_2") (pintype "passive"))
      (node (ref "IC6") (pin "13") (pinfunction "VC3_13") (pintype "passive"))
      (node (ref "R44") (pin "2") (pinfunction "2_2") (pintype "passive"))
    )
    (net (code "103") (name "Net-(IC6-VC4)") (class "Default")
      (node (ref "C48") (pin "2") (pinfunction "2_2") (pintype "passive"))
      (node (ref "C49") (pin "2") (pinfunction "2_2") (pintype "passive"))
      (node (ref "C50") (pin "2") (pinfunction "2_2") (pintype "passive"))
      (node (ref "IC6") (pin "12") (pinfunction "VC4_12") (pintype "passive"))
      (node (ref "IC6") (pin "7") (pinfunction "VSS_7") (pintype "passive"))
      (node (ref "R48") (pin "1") (pinfunction "1_1") (pintype "passive"))
      (node (ref "R51") (pin "1") (pinfunction "1_1") (pintype "passive"))
      (node (ref "R53") (pin "1") (pinfunction "1_1") (pintype "passive"))
    )
    (net (code "104") (name "Net-(IC6-VINI)") (class "Default")
      (node (ref "IC6") (pin "4") (pinfunction "VINI_4") (pintype "passive"))
      (node (ref "R47") (pin "2") (pinfunction "2_2") (pintype "passive"))
    )
    (net (code "105") (name "Net-(IC6-VMP)") (class "Default")
      (node (ref "IC6") (pin "2") (pinfunction "VMP_2") (pintype "passive"))
      (node (ref "R38") (pin "2") (pinfunction "2_2") (pintype "passive"))
    )
    (net (code "106") (name "Net-(IC7-OUT)") (class "Default")
      (node (ref "IC7") (pin "6") (pinfunction "OUT_6") (pintype "passive"))
      (node (ref "Q15") (pin "1") (pinfunction "G_1") (pintype "passive"))
    )
    (net (code "107") (name "Net-(IC7-VDD)") (class "Default")
      (node (ref "C52") (pin "2") (pinfunction "2_2") (pintype "passive"))
      (node (ref "IC7") (pin "2") (pinfunction "VDD_2") (pintype "passive"))
      (node (ref "R49") (pin "2") (pinfunction "2_2") (pintype "passive"))
    )
    (net (code "108") (name "Net-(IC8-OUT)") (class "Default")
      (node (ref "IC8") (pin "6") (pinfunction "OUT_6") (pintype "passive"))
      (node (ref "Q16") (pin "1") (pinfunction "G_1") (pintype "passive"))
    )
    (net (code "109") (name "Net-(IC8-VDD)") (class "Default")
      (node (ref "C57") (pin "2") (pinfunction "2_2") (pintype "passive"))
      (node (ref "IC8") (pin "2") (pinfunction "VDD_2") (pintype "passive"))
      (node (ref "R62") (pin "2") (pinfunction "2_2") (pintype "passive"))
    )
    (net (code "110") (name "Net-(IC8-VSS)") (class "Default")
      (node (ref "B1") (pin "6") (pinfunction "-_6") (pintype "passive"))
      (node (ref "C53") (pin "2") (pinfunction "2_2") (pintype "passive"))
      (node (ref "C57") (pin "1") (pinfunction "1_1") (pintype "passive"))
      (node (ref "IC8") (pin "3") (pinfunction "VSS_3") (pintype "passive"))
      (node (ref "Q16") (pin "2") (pinfunction "S_2") (pintype "passive"))
      (node (ref "R53") (pin "2") (pinfunction "2_2") (pintype "passive"))
      (node (ref "R54") (pin "1") (pinfunction "1_1") (pintype "passive"))
    )
    (net (code "111") (name "Net-(IC9-X1)") (class "Default")
      (node (ref "IC9") (pin "1") (pinfunction "X1_1") (pintype "passive"))
      (node (ref "X1") (pin "1") (pinfunction "1_1") (pintype "passive"))
    )
    (net (code "112") (name "Net-(IC9-X2)") (class "Default")
      (node (ref "IC9") (pin "2") (pinfunction "X2_2") (pintype "passive"))
      (node (ref "X1") (pin "2") (pinfunction "2_2") (pintype "passive"))
    )
    (net (code "113") (name "Net-(Q1-G)") (class "Default")
      (node (ref "Q1") (pin "4") (pinfunction "G_4") (pintype "passive"))
      (node (ref "U4") (pin "28") (pinfunction "HD_28") (pintype "passive"))
    )
    (net (code "114") (name "Net-(Q2-G)") (class "Default")
      (node (ref "Q2") (pin "1") (pinfunction "G_1") (pintype "passive"))
      (node (ref "Q6") (pin "3") (pinfunction "C_3") (pintype "passive"))
      (node (ref "R11") (pin "2") (pinfunction "2_2") (pintype "passive"))
    )
    (net (code "115") (name "Net-(Q3-B)") (class "Default")
      (node (ref "Q3") (pin "1") (pinfunction "B_1") (pintype "passive"))
      (node (ref "R6") (pin "2") (pinfunction "2_2") (pintype "passive"))
    )
    (net (code "116") (name "Net-(Q3-E)") (class "Default")
      (node (ref "Q3") (pin "2") (pinfunction "E_2") (pintype "passive"))
      (node (ref "R8") (pin "1") (pinfunction "1_1") (pintype "passive"))
      (node (ref "U3") (pin "14") (pinfunction "RTS#_14") (pintype "passive"))
    )
    (net (code "117") (name "Net-(Q4-G)") (class "Default")
      (node (ref "Q4") (pin "4") (pinfunction "G_4") (pintype "passive"))
      (node (ref "U4") (pin "26") (pinfunction "LD_26") (pintype "passive"))
    )
    (net (code "118") (name "Net-(Q5-B)") (class "Default")
      (node (ref "Q5") (pin "1") (pinfunction "B_1") (pintype "passive"))
      (node (ref "R8") (pin "2") (pinfunction "2_2") (pintype "passive"))
    )
    (net (code "119") (name "Net-(Q5-C)") (class "Default")
      (node (ref "Q5") (pin "3") (pinfunction "C_3") (pintype "passive"))
      (node (ref "R10") (pin "1") (pinfunction "1_1") (pintype "passive"))
    )
    (net (code "120") (name "Net-(Q6-B)") (class "Default")
      (node (ref "Q6") (pin "1") (pinfunction "B_1") (pintype "passive"))
      (node (ref "R12") (pin "2") (pinfunction "2_2") (pintype "passive"))
      (node (ref "R13") (pin "2") (pinfunction "2_2") (pintype "passive"))
    )
    (net (code "121") (name "Net-(Q11-D)") (class "Default")
      (node (ref "Q11") (pin "2") (pinfunction "D_2") (pintype "passive"))
      (node (ref "Q12") (pin "2") (pinfunction "D_2") (pintype "passive"))
    )
    (net (code "122") (name "Net-(Q12-G)") (class "Default")
      (node (ref "Q12") (pin "1") (pinfunction "G_1") (pintype "passive"))
      (node (ref "R41") (pin "2") (pinfunction "2_2") (pintype "passive"))
    )
    (net (code "123") (name "Net-(Q13-D)") (class "Default")
      (node (ref "Q13") (pin "3") (pinfunction "D_3") (pintype "passive"))
      (node (ref "R35") (pin "2") (pinfunction "2_2") (pintype "passive"))
    )
    (net (code "124") (name "Net-(Q14-D)") (class "Default")
      (node (ref "FAN") (pin "2") (pinfunction "2_2") (pintype "passive"))
      (node (ref "Q14") (pin "3") (pinfunction "D_3") (pintype "passive"))
    )
    (net (code "125") (name "Net-(Q14-G)") (class "Default")
      (node (ref "Q14") (pin "1") (pinfunction "G_1") (pintype "passive"))
      (node (ref "R40") (pin "1") (pinfunction "1_1") (pintype "passive"))
    )
    (net (code "126") (name "Net-(Q15-D)") (class "Default")
      (node (ref "Q15") (pin "3") (pinfunction "D_3") (pintype "passive"))
      (node (ref "R45") (pin "2") (pinfunction "2_2") (pintype "passive"))
    )
    (net (code "127") (name "Net-(Q16-D)") (class "Default")
      (node (ref "Q16") (pin "3") (pinfunction "D_3") (pintype "passive"))
      (node (ref "R55") (pin "2") (pinfunction "2_2") (pintype "passive"))
    )
    (net (code "128") (name "Net-(Q17-D)") (class "Default")
      (node (ref "Q17") (pin "2") (pinfunction "D_2") (pintype "passive"))
      (node (ref "Q18") (pin "2") (pinfunction "D_2") (pintype "passive"))
    )
    (net (code "129") (name "Net-(Q19-B)") (class "Default")
      (node (ref "Q19") (pin "1") (pinfunction "B_1") (pintype "passive"))
      (node (ref "R58") (pin "2") (pinfunction "2_2") (pintype "passive"))
      (node (ref "R70") (pin "2") (pinfunction "2_2") (pintype "passive"))
    )
    (net (code "130") (name "Net-(Q20-B)") (class "Default")
      (node (ref "Q20") (pin "1") (pinfunction "B_1") (pintype "passive"))
      (node (ref "R71") (pin "2") (pinfunction "2_2") (pintype "passive"))
      (node (ref "R72") (pin "2") (pinfunction "2_2") (pintype "passive"))
    )
    (net (code "131") (name "Net-(TYPEC1-CC1)") (class "Default")
      (node (ref "R73") (pin "1") (pinfunction "1_1") (pintype "passive"))
      (node (ref "TYPEC1") (pin "A5") (pinfunction "CC1_A5") (pintype "passive"))
    )
    (net (code "132") (name "Net-(TYPEC1-CC2)") (class "Default")
      (node (ref "R74") (pin "2") (pinfunction "2_2") (pintype "passive"))
      (node (ref "TYPEC1") (pin "B5") (pinfunction "CC2_B5") (pintype "passive"))
    )
    (net (code "133") (name "Net-(U1-OSC_IN)") (class "Default")
      (node (ref "C17") (pin "2") (pinfunction "2_2") (pintype "passive"))
      (node (ref "U1") (pin "5") (pinfunction "OSC_IN_5") (pintype "input"))
      (node (ref "X2") (pin "1") (pinfunction "1_1") (pintype "passive"))
    )
    (net (code "134") (name "Net-(U1-OSC_OUT)") (class "Default")
      (node (ref "C19") (pin "1") (pinfunction "1_1") (pintype "passive"))
      (node (ref "U1") (pin "6") (pinfunction "OSC_OUT_6") (pintype "output"))
      (node (ref "X2") (pin "2") (pinfunction "2_2") (pintype "passive"))
    )
    (net (code "135") (name "Net-(U1-VDDA)") (class "Default")
      (node (ref "C33") (pin "2") (pinfunction "2_2") (pintype "passive"))
      (node (ref "L4") (pin "2") (pinfunction "2_2") (pintype "passive"))
      (node (ref "U1") (pin "13") (pinfunction "VDDA_13") (pintype "power_in"))
    )
    (net (code "136") (name "Net-(U2-VBUS)") (class "Default")
      (node (ref "C5") (pin "2") (pinfunction "2_2") (pintype "passive"))
      (node (ref "CON1") (pin "1") (pintype "power_in"))
      (node (ref "RF1") (pin "2") (pinfunction "2_2") (pintype "passive"))
      (node (ref "TYPEC2") (pin "A4") (pinfunction "VBUS_A4") (pintype "passive"))
      (node (ref "TYPEC2") (pin "A9") (pinfunction "VBUS_A9") (pintype "passive"))
      (node (ref "TYPEC2") (pin "B4") (pinfunction "VBUS_B4") (pintype "passive"))
      (node (ref "TYPEC2") (pin "B9") (pinfunction "VBUS_B9") (pintype "passive"))
      (node (ref "U2") (pin "16") (pinfunction "VBUS_16") (pintype "passive"))
      (node (ref "U2") (pin "2") (pinfunction "VIN_2") (pintype "passive"))
    )
    (net (code "137") (name "Net-(U3-DTR#)") (class "Default")
      (node (ref "R6") (pin "1") (pinfunction "1_1") (pintype "passive"))
      (node (ref "U3") (pin "13") (pinfunction "DTR#_13") (pintype "passive"))
    )
    (net (code "138") (name "Net-(U3-V3)") (class "Default")
      (node (ref "C4") (pin "2") (pinfunction "2_2") (pintype "passive"))
      (node (ref "U3") (pin "4") (pinfunction "V3_4") (pintype "passive"))
    )
    (net (code "139") (name "Net-(U3-XI)") (class "Default")
      (node (ref "C9") (pin "2") (pinfunction "2_2") (pintype "passive"))
      (node (ref "U3") (pin "7") (pinfunction "XI_7") (pintype "passive"))
      (node (ref "X3") (pin "1") (pinfunction "1_1") (pintype "passive"))
    )
    (net (code "140") (name "Net-(U3-XO)") (class "Default")
      (node (ref "C20") (pin "2") (pinfunction "2_2") (pintype "passive"))
      (node (ref "U3") (pin "8") (pinfunction "XO_8") (pintype "passive"))
      (node (ref "X3") (pin "2") (pinfunction "2_2") (pintype "passive"))
    )
    (net (code "141") (name "Net-(U4-BT)") (class "Default")
      (node (ref "C10") (pin "2") (pinfunction "2_2") (pintype "passive"))
      (node (ref "U4") (pin "29") (pinfunction "BT_29") (pintype "passive"))
    )
    (net (code "142") (name "Net-(U4-COMP)") (class "Default")
      (node (ref "R65") (pin "2") (pinfunction "2_2") (pintype "passive"))
      (node (ref "U4") (pin "17") (pinfunction "COMP_17") (pintype "passive"))
    )
    (net (code "143") (name "Net-(U4-SNS1N)") (class "Default")
      (node (ref "C6") (pin "2") (pinfunction "2_2") (pintype "passive"))
      (node (ref "R5") (pin "1") (pinfunction "1_1") (pintype "passive"))
      (node (ref "U4") (pin "31") (pinfunction "SNS1N_31") (pintype "passive"))
    )
    (net (code "144") (name "Net-(U4-SNS1P)") (class "Default")
      (node (ref "C6") (pin "1") (pinfunction "1_1") (pintype "passive"))
      (node (ref "R4") (pin "1") (pinfunction "1_1") (pintype "passive"))
      (node (ref "U4") (pin "32") (pinfunction "SNS1P_32") (pintype "passive"))
    )
    (net (code "145") (name "Net-(U4-SNS2P)") (class "Default")
      (node (ref "L1") (pin "2") (pinfunction "2_2") (pintype "passive"))
      (node (ref "R7") (pin "1") (pinfunction "1_1") (pintype "passive"))
      (node (ref "U4") (pin "20") (pinfunction "SNS2P_20") (pintype "passive"))
    )
    (net (code "146") (name "Net-(U5-+)") (class "Default")
      (node (ref "R28") (pin "2") (pinfunction "2_2") (pintype "passive"))
      (node (ref "U5") (pin "3") (pinfunction "+_3") (pintype "passive"))
    )
    (net (code "147") (name "Net-(U5-IN-)") (class "Default")
      (node (ref "R33") (pin "2") (pinfunction "2_2") (pintype "passive"))
      (node (ref "R34") (pin "1") (pinfunction "1_1") (pintype "passive"))
      (node (ref "U5") (pin "4") (pinfunction "IN-_4") (pintype "passive"))
    )
    (net (code "148") (name "Net-(U6-BP)") (class "Default")
      (node (ref "C56") (pin "2") (pinfunction "2_2") (pintype "passive"))
      (node (ref "U6") (pin "4") (pinfunction "BP_4") (pintype "passive"))
    )
    (net (code "149") (name "SW") (class "Default")
      (node (ref "C10") (pin "1") (pinfunction "1_1") (pintype "passive"))
      (node (ref "L1") (pin "1") (pinfunction "1_1") (pintype "passive"))
      (node (ref "Q1") (pin "1") (pinfunction "S_1") (pintype "passive"))
      (node (ref "Q1") (pin "2") (pinfunction "S_2") (pintype "passive"))
      (node (ref "Q1") (pin "3") (pinfunction "S_3") (pintype "passive"))
      (node (ref "Q4") (pin "5") (pinfunction "D_5") (pintype "passive"))
      (node (ref "Q4") (pin "6") (pinfunction "D_6") (pintype "passive"))
      (node (ref "Q4") (pin "7") (pinfunction "D_7") (pintype "passive"))
      (node (ref "Q4") (pin "8") (pinfunction "D_8") (pintype "passive"))
      (node (ref "U4") (pin "27") (pinfunction "SW_27") (pintype "passive"))
    )
    (net (code "150") (name "TC_VCC") (class "Default")
      (node (ref "D1") (pin "1") (pinfunction "A_1") (pintype "passive"))
      (node (ref "TYPEC1") (pin "A4") (pinfunction "VBUS_A4") (pintype "passive"))
      (node (ref "TYPEC1") (pin "A9") (pinfunction "VBUS_A9") (pintype "passive"))
      (node (ref "TYPEC1") (pin "B4") (pinfunction "VBUS_B4") (pintype "passive"))
      (node (ref "TYPEC1") (pin "B9") (pinfunction "VBUS_B9") (pintype "passive"))
      (node (ref "U3") (pin "16") (pinfunction "Vcc_16") (pintype "passive"))
    )
    (net (code "151") (name "VBUS") (class "Default")
      (node (ref "E3") (pin "1") (pinfunction "A_1") (pintype "passive"))
      (node (ref "E4") (pin "1") (pinfunction "A_1") (pintype "passive"))
      (node (ref "E9") (pin "1") (pinfunction "A_1") (pintype "passive"))
      (node (ref "EK2") (pin "2") (pinfunction "2_2") (pintype "passive"))
      (node (ref "Q1") (pin "5") (pinfunction "D_5") (pintype "passive"))
      (node (ref "Q1") (pin "6") (pinfunction "D_6") (pintype "passive"))
      (node (ref "Q1") (pin "7") (pinfunction "D_7") (pintype "passive"))
      (node (ref "Q1") (pin "8") (pinfunction "D_8") (pintype "passive"))
      (node (ref "Q2") (pin "3") (pinfunction "S_3") (pintype "passive"))
      (node (ref "Q7") (pin "5") (pinfunction "D_5") (pintype "passive"))
      (node (ref "Q7") (pin "6") (pinfunction "D_6") (pintype "passive"))
      (node (ref "Q7") (pin "7") (pinfunction "D_7") (pintype "passive"))
      (node (ref "Q7") (pin "8") (pinfunction "D_8") (pintype "passive"))
      (node (ref "R11") (pin "1") (pinfunction "1_1") (pintype "passive"))
      (node (ref "R2") (pin "2") (pinfunction "2_2") (pintype "passive"))
      (node (ref "R21") (pin "1") (pinfunction "1_1") (pintype "passive"))
      (node (ref "R5") (pin "2") (pinfunction "2_2") (pintype "passive"))
    )
    (net (code "152") (name "VDRV") (class "Default")
      (node (ref "C12") (pin "2") (pinfunction "2_2") (pintype "passive"))
      (node (ref "C13") (pin "2") (pinfunction "2_2") (pintype "passive"))
      (node (ref "U4") (pin "23") (pinfunction "VCC_23") (pintype "passive"))
      (node (ref "U4") (pin "24") (pinfunction "VDRV_24") (pintype "passive"))
    )
    (net (code "153") (name "VIN") (class "Default")
      (node (ref "C11") (pin "1") (pinfunction "1_1") (pintype "passive"))
      (node (ref "DZ2") (pin "2") (pinfunction "K_2") (pintype "passive"))
      (node (ref "E1") (pin "1") (pinfunction "A_1") (pintype "passive"))
      (node (ref "EK4") (pin "1") (pinfunction "1_1") (pintype "passive"))
      (node (ref "Q18") (pin "3") (pinfunction "S_3") (pintype "passive"))
      (node (ref "R2") (pin "1") (pinfunction "1_1") (pintype "passive"))
      (node (ref "R4") (pin "2") (pinfunction "2_2") (pintype "passive"))
      (node (ref "R69") (pin "2") (pinfunction "2_2") (pintype "passive"))
      (node (ref "U4") (pin "30") (pinfunction "VBUS_30") (pintype "passive"))
    )
    (net (code "154") (name "VIN_DC") (class "Default")
      (node (ref "D5") (pin "1") (pinfunction "A_1") (pintype "passive"))
      (node (ref "DZ1") (pin "2") (pinfunction "K_2") (pintype "passive"))
      (node (ref "Q17") (pin "3") (pinfunction "S_3") (pintype "passive"))
      (node (ref "R14") (pin "2") (pinfunction "2_2") (pintype "passive"))
      (node (ref "R57") (pin "1") (pinfunction "1_1") (pintype "passive"))
      (node (ref "RF1") (pin "1") (pinfunction "1_1") (pintype "passive"))
    )
    (net (code "155") (name "VIN_DEC") (class "Default")
      (node (ref "R57") (pin "2") (pinfunction "2_2") (pintype "passive"))
      (node (ref "R64") (pin "1") (pinfunction "1_1") (pintype "passive"))
      (node (ref "U1") (pin "16") (pinfunction "USART2_TX/PA2_16") (pintype "bidirectional"))
    )
    (net (code "156") (name "VOUT") (class "Default")
      (node (ref "C3") (pin "1") (pinfunction "1_1") (pintype "passive"))
      (node (ref "C35") (pin "1") (pinfunction "1_1") (pintype "passive"))
      (node (ref "C38") (pin "1") (pinfunction "1_1") (pintype "passive"))
      (node (ref "D10") (pin "3") (pinfunction "HEATSINK_3") (pintype "passive"))
      (node (ref "E5") (pin "1") (pinfunction "A_1") (pintype "passive"))
      (node (ref "E6") (pin "1") (pinfunction "A_1") (pintype "passive"))
      (node (ref "E8") (pin "1") (pinfunction "A_1") (pintype "passive"))
      (node (ref "EK1") (pin "2") (pinfunction "2_2") (pintype "passive"))
      (node (ref "IC1") (pin "8") (pinfunction "VBUS_8") (pintype "passive"))
      (node (ref "JP3") (pin "1") (pinfunction "1_1") (pintype "passive"))
      (node (ref "JP3") (pin "2") (pinfunction "2_2") (pintype "passive"))
      (node (ref "JP3") (pin "3") (pinfunction "3_3") (pintype "passive"))
      (node (ref "JP3") (pin "4") (pinfunction "4_4") (pintype "passive"))
      (node (ref "JP3") (pin "5") (pinfunction "5_5") (pintype "passive"))
      (node (ref "JP3") (pin "6") (pinfunction "6_6") (pintype "passive"))
      (node (ref "Q8") (pin "5") (pinfunction "D_5") (pintype "passive"))
      (node (ref "Q8") (pin "6") (pinfunction "D_6") (pintype "passive"))
      (node (ref "Q8") (pin "7") (pinfunction "D_7") (pintype "passive"))
      (node (ref "Q8") (pin "8") (pinfunction "D_8") (pintype "passive"))
      (node (ref "R25") (pin "2") (pinfunction "2_2") (pintype "passive"))
      (node (ref "R46") (pin "2") (pinfunction "2_2") (pintype "passive"))
    )
    (net (code "157") (name "VOUT_DEC") (class "Default")
      (node (ref "R56") (pin "2") (pinfunction "2_2") (pintype "passive"))
      (node (ref "R63") (pin "1") (pinfunction "1_1") (pintype "passive"))
      (node (ref "U1") (pin "8") (pinfunction "ADC123_IN10/PC0_8") (pintype "bidirectional"))
    )
    (net (code "158") (name "VOUT_GND") (class "Default")
      (node (ref "IC1") (pin "10") (pinfunction "IN+_10") (pintype "passive"))
      (node (ref "JP3") (pin "10") (pinfunction "10_10") (pintype "passive"))
      (node (ref "JP3") (pin "11") (pinfunction "11_11") (pintype "passive"))
      (node (ref "JP3") (pin "12") (pinfunction "12_12") (pintype "passive"))
      (node (ref "JP3") (pin "7") (pinfunction "7_7") (pintype "passive"))
      (node (ref "JP3") (pin "8") (pinfunction "8_8") (pintype "passive"))
      (node (ref "JP3") (pin "9") (pinfunction "9_9") (pintype "passive"))
      (node (ref "R28") (pin "1") (pinfunction "1_1") (pintype "passive"))
      (node (ref "R30") (pin "2") (pinfunction "2_2") (pintype "passive"))
    )
    (net (code "159") (name "VOUT_OUT") (class "Default")
      (node (ref "JP3") (pin "15") (pinfunction "15_15") (pintype "passive"))
      (node (ref "R56") (pin "1") (pinfunction "1_1") (pintype "passive"))
    )
    (net (code "160") (name "unconnected-(CON1-Pad0)") (class "Default")
      (node (ref "CON1") (pin "0") (pintype "power_in"))
    )
    (net (code "161") (name "unconnected-(IC1-ALERT-Pad3)") (class "Default")
      (node (ref "IC1") (pin "3") (pinfunction "ALERT_3") (pintype "passive+no_connect"))
    )
    (net (code "162") (name "unconnected-(IC5-NC_1-Pad1)") (class "Default")
      (node (ref "IC5") (pin "1") (pinfunction "NC_1_1") (pintype "passive+no_connect"))
    )
    (net (code "163") (name "unconnected-(IC5-NC_2-Pad4)") (class "Default")
      (node (ref "IC5") (pin "4") (pinfunction "NC_2_4") (pintype "passive+no_connect"))
    )
    (net (code "164") (name "unconnected-(IC5-NC_3-Pad5)") (class "Default")
      (node (ref "IC5") (pin "5") (pinfunction "NC_3_5") (pintype "passive+no_connect"))
    )
    (net (code "165") (name "unconnected-(IC6-NC_1-Pad8)") (class "Default")
      (node (ref "IC6") (pin "8") (pinfunction "NC_1_8") (pintype "passive+no_connect"))
    )
    (net (code "166") (name "unconnected-(IC6-NC_2-Pad9)") (class "Default")
      (node (ref "IC6") (pin "9") (pinfunction "NC_2_9") (pintype "passive+no_connect"))
    )
    (net (code "167") (name "unconnected-(IC7-NC_1-Pad1)") (class "Default")
      (node (ref "IC7") (pin "1") (pinfunction "NC_1_1") (pintype "passive+no_connect"))
    )
    (net (code "168") (name "unconnected-(IC7-NC_2-Pad4)") (class "Default")
      (node (ref "IC7") (pin "4") (pinfunction "NC_2_4") (pintype "passive+no_connect"))
    )
    (net (code "169") (name "unconnected-(IC7-NC_3-Pad5)") (class "Default")
      (node (ref "IC7") (pin "5") (pinfunction "NC_3_5") (pintype "passive+no_connect"))
    )
    (net (code "170") (name "unconnected-(IC8-NC_1-Pad1)") (class "Default")
      (node (ref "IC8") (pin "1") (pinfunction "NC_1_1") (pintype "passive+no_connect"))
    )
    (net (code "171") (name "unconnected-(IC8-NC_2-Pad4)") (class "Default")
      (node (ref "IC8") (pin "4") (pinfunction "NC_2_4") (pintype "passive+no_connect"))
    )
    (net (code "172") (name "unconnected-(IC8-NC_3-Pad5)") (class "Default")
      (node (ref "IC8") (pin "5") (pinfunction "NC_3_5") (pintype "passive+no_connect"))
    )
    (net (code "173") (name "unconnected-(IC9-SQW{slash}OUT-Pad7)") (class "Default")
      (node (ref "IC9") (pin "7") (pinfunction "SQW/OUT_7") (pintype "passive+no_connect"))
    )
    (net (code "174") (name "unconnected-(TYPEC1-SBU1-PadA8)") (class "Default")
      (node (ref "TYPEC1") (pin "A8") (pinfunction "SBU1_A8") (pintype "passive+no_connect"))
    )
    (net (code "175") (name "unconnected-(TYPEC1-SBU2-PadD8)") (class "Default")
      (node (ref "TYPEC1") (pin "D8") (pinfunction "SBU2_D8") (pintype "passive+no_connect"))
    )
    (net (code "176") (name "unconnected-(TYPEC2-DN1-PadA7)") (class "Default")
      (node (ref "TYPEC2") (pin "A7") (pinfunction "DN1_A7") (pintype "passive+no_connect"))
    )
    (net (code "177") (name "unconnected-(TYPEC2-DN2-PadB7)") (class "Default")
      (node (ref "TYPEC2") (pin "B7") (pinfunction "DN2_B7") (pintype "passive+no_connect"))
    )
    (net (code "178") (name "unconnected-(TYPEC2-DP1-PadA6)") (class "Default")
      (node (ref "TYPEC2") (pin "A6") (pinfunction "DP1_A6") (pintype "passive+no_connect"))
    )
    (net (code "179") (name "unconnected-(TYPEC2-DP2-PadB6)") (class "Default")
      (node (ref "TYPEC2") (pin "B6") (pinfunction "DP2_B6") (pintype "passive+no_connect"))
    )
    (net (code "180") (name "unconnected-(TYPEC2-SBU1-PadA8)") (class "Default")
      (node (ref "TYPEC2") (pin "A8") (pinfunction "SBU1_A8") (pintype "passive+no_connect"))
    )
    (net (code "181") (name "unconnected-(TYPEC2-SBU2-PadD8)") (class "Default")
      (node (ref "TYPEC2") (pin "D8") (pinfunction "SBU2_D8") (pintype "passive+no_connect"))
    )
    (net (code "182") (name "unconnected-(U1-CAN_RX{slash}PA11-Pad44)") (class "Default")
      (node (ref "U1") (pin "44") (pinfunction "CAN_RX/PA11_44") (pintype "bidirectional+no_connect"))
    )
    (net (code "183") (name "unconnected-(U1-CAN_TX_{slash}PA12-Pad45)") (class "Default")
      (node (ref "U1") (pin "45") (pinfunction "CAN_TX_/PA12_45") (pintype "bidirectional+no_connect"))
    )
    (net (code "184") (name "unconnected-(U1-SPI3_MISO{slash}NJTRST{slash}PB4-Pad56)") (class "Default")
      (node (ref "U1") (pin "56") (pinfunction "SPI3_MISO/NJTRST/PB4_56") (pintype "bidirectional+no_connect"))
    )
    (net (code "185") (name "unconnected-(U2-NC-Pad3)") (class "Default")
      (node (ref "U2") (pin "3") (pinfunction "NC_3") (pintype "passive+no_connect"))
    )
    (net (code "186") (name "unconnected-(U2-NC-Pad4)") (class "Default")
      (node (ref "U2") (pin "4") (pinfunction "NC_4") (pintype "passive+no_connect"))
    )
    (net (code "187") (name "unconnected-(U2-NC-Pad9)") (class "Default")
      (node (ref "U2") (pin "9") (pinfunction "NC_9") (pintype "passive+no_connect"))
    )
    (net (code "188") (name "unconnected-(U2-NC-Pad10)") (class "Default")
      (node (ref "U2") (pin "10") (pinfunction "NC_10") (pintype "passive+no_connect"))
    )
    (net (code "189") (name "unconnected-(U2-NC-Pad14)") (class "Default")
      (node (ref "U2") (pin "14") (pinfunction "NC_14") (pintype "passive+no_connect"))
    )
    (net (code "190") (name "unconnected-(U2-NC-Pad15)") (class "Default")
      (node (ref "U2") (pin "15") (pinfunction "NC_15") (pintype "passive+no_connect"))
    )
    (net (code "191") (name "unconnected-(U2-TS1-Pad6)") (class "Default")
      (node (ref "U2") (pin "6") (pinfunction "TS1_6") (pintype "passive+no_connect"))
    )
    (net (code "192") (name "unconnected-(U2-TS2-Pad7)") (class "Default")
      (node (ref "U2") (pin "7") (pinfunction "TS2_7") (pintype "passive+no_connect"))
    )
    (net (code "193") (name "unconnected-(U2-TS3-Pad8)") (class "Default")
      (node (ref "U2") (pin "8") (pinfunction "TS3_8") (pintype "passive+no_connect"))
    )
    (net (code "194") (name "unconnected-(U2-VBUSG-Pad1)") (class "Default")
      (node (ref "U2") (pin "1") (pinfunction "VBUSG_1") (pintype "passive+no_connect"))
    )
    (net (code "195") (name "unconnected-(U3-CTS#-Pad9)") (class "Default")
      (node (ref "U3") (pin "9") (pinfunction "CTS#_9") (pintype "passive+no_connect"))
    )
    (net (code "196") (name "unconnected-(U3-DCD#-Pad12)") (class "Default")
      (node (ref "U3") (pin "12") (pinfunction "DCD#_12") (pintype "passive+no_connect"))
    )
    (net (code "197") (name "unconnected-(U3-DSR#-Pad10)") (class "Default")
      (node (ref "U3") (pin "10") (pinfunction "DSR#_10") (pintype "passive+no_connect"))
    )
    (net (code "198") (name "unconnected-(U3-RI#-Pad11)") (class "Default")
      (node (ref "U3") (pin "11") (pinfunction "RI#_11") (pintype "passive+no_connect"))
    )
    (net (code "199") (name "unconnected-(U3-RS232-Pad15)") (class "Default")
      (node (ref "U3") (pin "15") (pinfunction "RS232_15") (pintype "passive+no_connect"))
    )
    (net (code "200") (name "unconnected-(U4-ACIN-Pad6)") (class "Default")
      (node (ref "U4") (pin "6") (pinfunction "ACIN_6") (pintype "passive+no_connect"))
    )
    (net (code "201") (name "unconnected-(U4-CP-Pad2)") (class "Default")
      (node (ref "U4") (pin "2") (pinfunction "CP_2") (pintype "passive+no_connect"))
    )
    (net (code "202") (name "unconnected-(U4-DM-Pad15)") (class "Default")
      (node (ref "U4") (pin "15") (pinfunction "DM_15") (pintype "passive+no_connect"))
    )
    (net (code "203") (name "unconnected-(U4-DP-Pad14)") (class "Default")
      (node (ref "U4") (pin "14") (pinfunction "DP_14") (pintype "passive+no_connect"))
    )
    (net (code "204") (name "unconnected-(U4-FB-Pad16)") (class "Default")
      (node (ref "U4") (pin "16") (pinfunction "FB_16") (pintype "passive+no_connect"))
    )
    (net (code "205") (name "unconnected-(U4-GPO-Pad1)") (class "Default")
      (node (ref "U4") (pin "1") (pinfunction "GPO_1") (pintype "passive+no_connect"))
    )
    (net (code "206") (name "unconnected-(U4-INDET1-Pad3)") (class "Default")
      (node (ref "U4") (pin "3") (pinfunction "INDET1_3") (pintype "passive+no_connect"))
    )
    (net (code "207") (name "unconnected-(U4-INDET2-Pad5)") (class "Default")
      (node (ref "U4") (pin "5") (pinfunction "INDET2_5") (pintype "passive+no_connect"))
    )
    (net (code "208") (name "unconnected-(U4-INT-Pad11)") (class "Default")
      (node (ref "U4") (pin "11") (pinfunction "INT_11") (pintype "passive+no_connect"))
    )
    (net (code "209") (name "unconnected-(U4-NC-Pad22)") (class "Default")
      (node (ref "U4") (pin "22") (pinfunction "NC_22") (pintype "passive+no_connect"))
    )
    (net (code "210") (name "unconnected-(U4-PGGATE{slash}DITHER-Pad4)") (class "Default")
      (node (ref "U4") (pin "4") (pinfunction "PGGATE/DITHER_4") (pintype "passive+no_connect"))
    )
  )
)
